# Connectors.net
KiCad netlist of a schematic drawn in Altium Designer
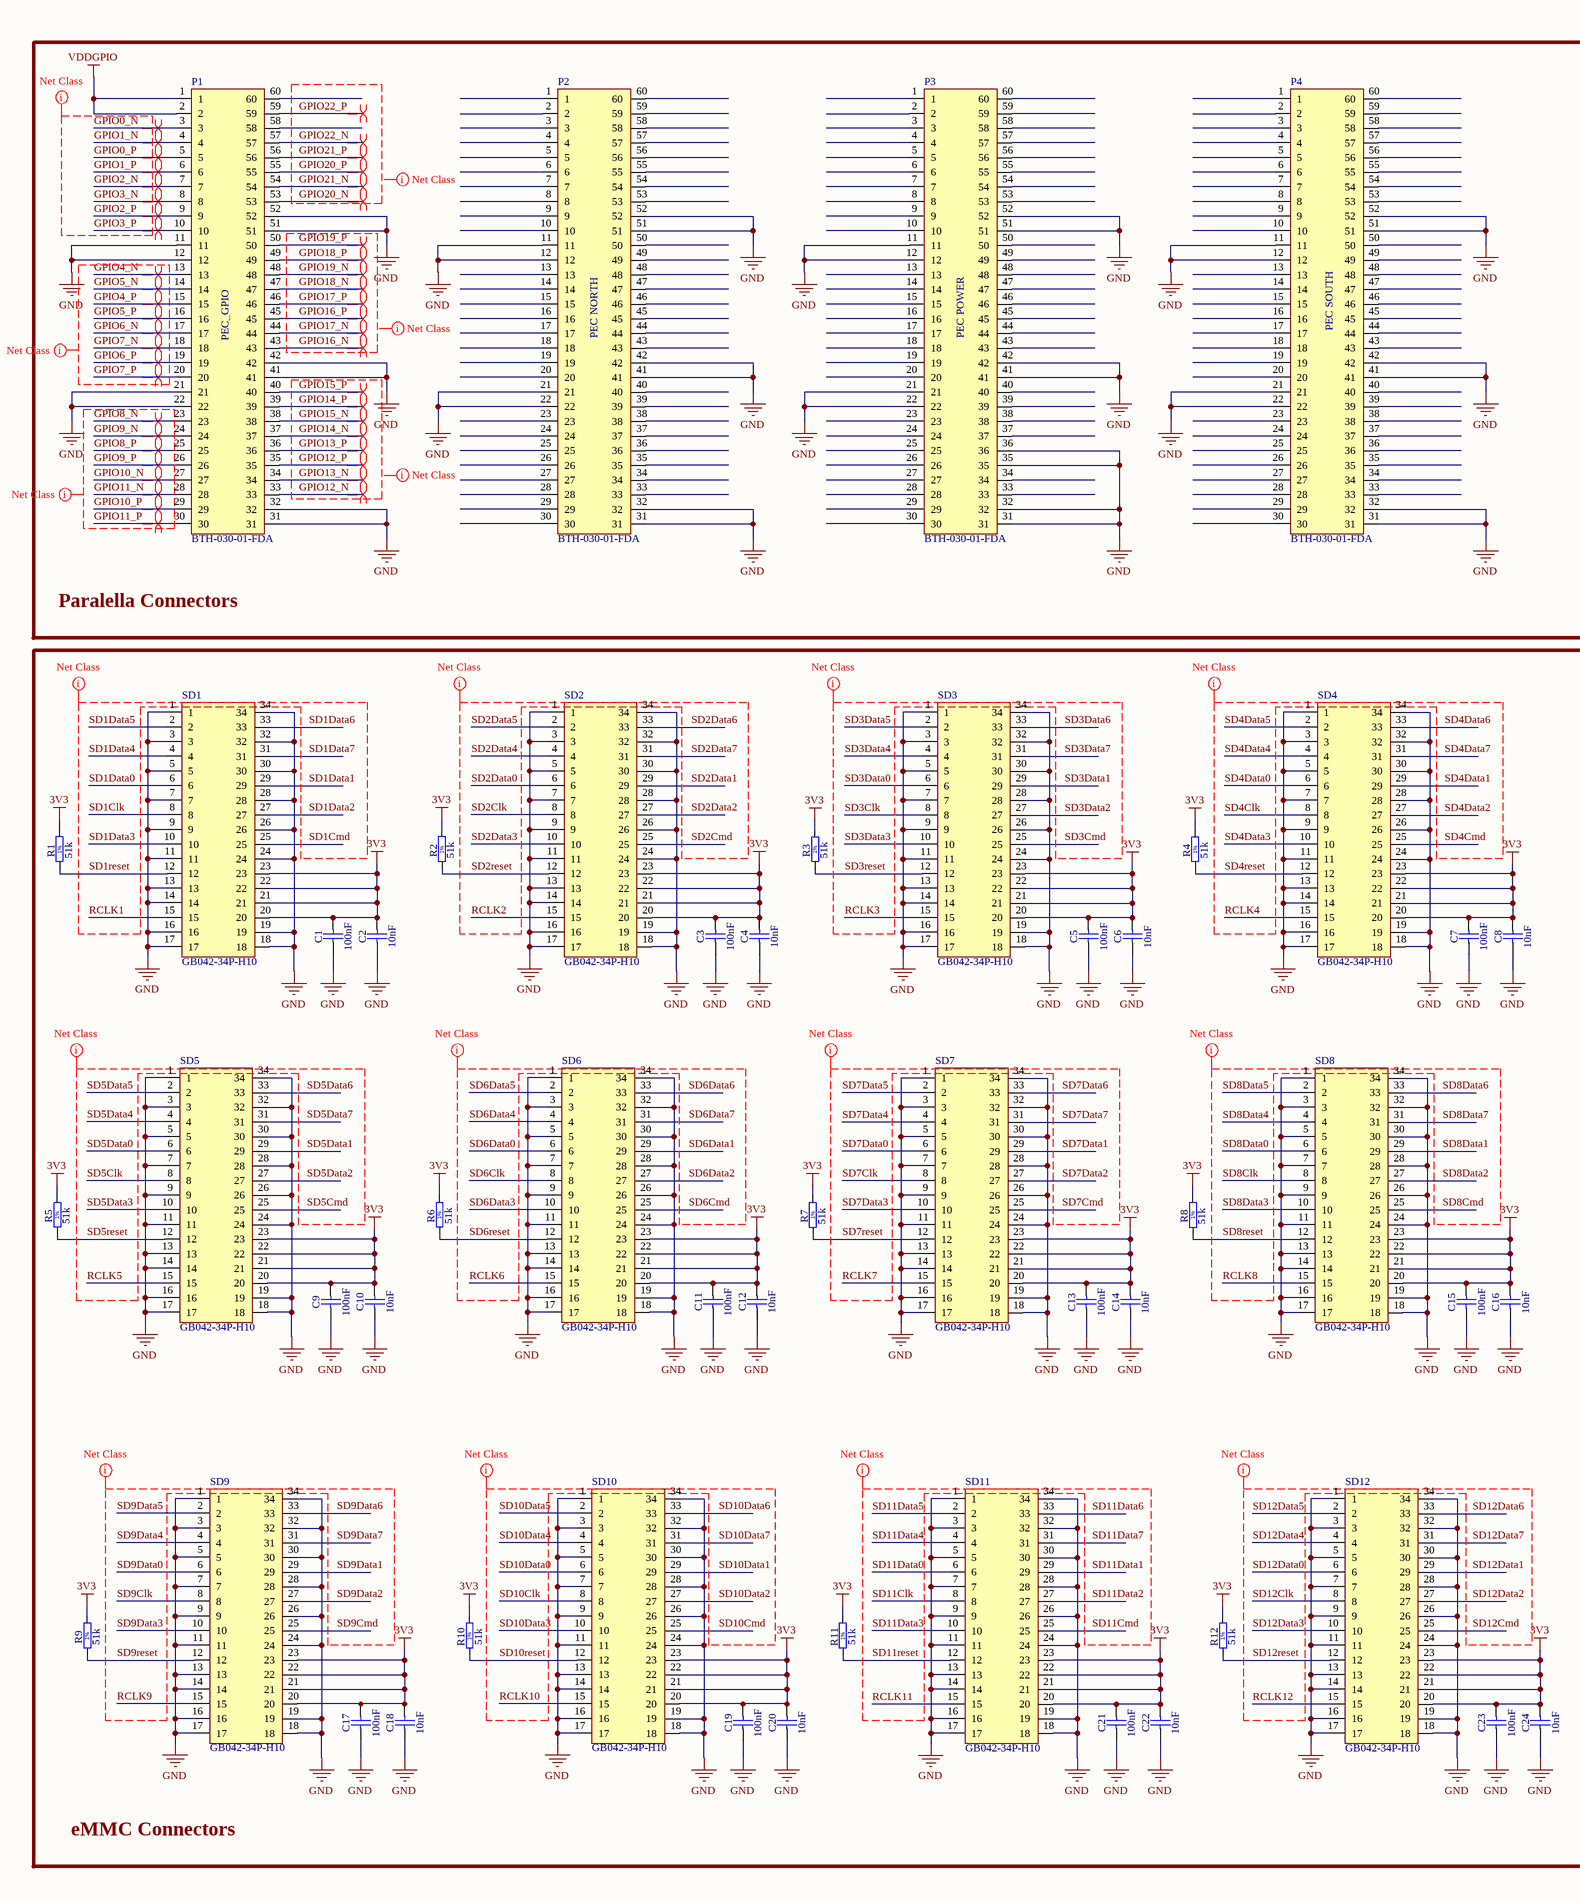
[diagram p0: Connectors.SchDoc, left]
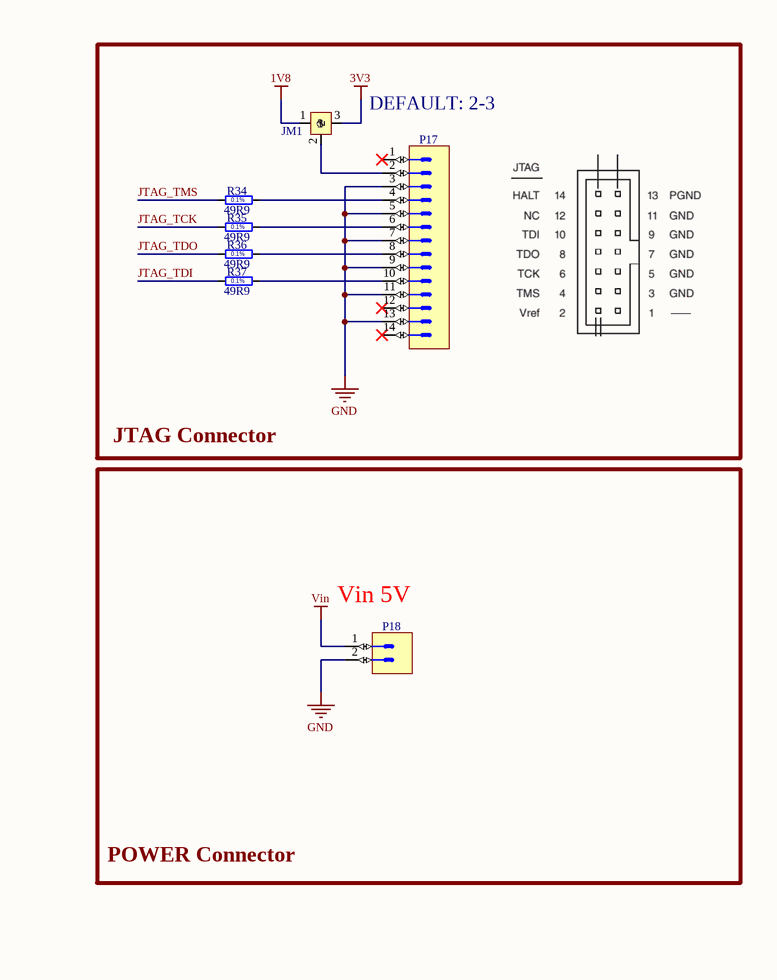
[diagram p1: Connectors.SchDoc, right]

(export (version "E")
  (design (tool "Eeschema 10.0.6"))
  (components
    (comp (ref "C1")
      (value "100nF")
      (footprint "CAPC1608X87N")
      (description "Non-polarised capacitor")
      (fields
        (field (name "PART NUMBER") "CC0603_100NF_50V_10%_X7R")
        (field (name "VOLTAGE") "50V")
        (field (name "AUTHOR") "CERN DEM JLC")
      )
      (libsource (lib "Capacitors") (part "Capacitor - non polarized"))
    )
    (comp (ref "C2")
      (value "10nF")
      (footprint "CAPC1608X87N")
      (description "Non-polarised capacitor")
      (fields
        (field (name "PART NUMBER") "CC0603_10NF_50V_10%_X7R")
        (field (name "VOLTAGE") "50V")
        (field (name "AUTHOR") "CERN DEM JLC")
      )
      (libsource (lib "Capacitors") (part "Capacitor - non polarized"))
    )
    (comp (ref "C3")
      (value "100nF")
      (footprint "CAPC1608X87N")
      (description "Non-polarised capacitor")
      (fields
        (field (name "PART NUMBER") "CC0603_100NF_50V_10%_X7R")
        (field (name "VOLTAGE") "50V")
        (field (name "AUTHOR") "CERN DEM JLC")
      )
      (libsource (lib "Capacitors") (part "Capacitor - non polarized"))
    )
    (comp (ref "C4")
      (value "10nF")
      (footprint "CAPC1608X87N")
      (description "Non-polarised capacitor")
      (fields
        (field (name "PART NUMBER") "CC0603_10NF_50V_10%_X7R")
        (field (name "VOLTAGE") "50V")
        (field (name "AUTHOR") "CERN DEM JLC")
      )
      (libsource (lib "Capacitors") (part "Capacitor - non polarized"))
    )
    (comp (ref "C5")
      (value "100nF")
      (footprint "CAPC1608X87N")
      (description "Non-polarised capacitor")
      (fields
        (field (name "PART NUMBER") "CC0603_100NF_50V_10%_X7R")
        (field (name "VOLTAGE") "50V")
        (field (name "AUTHOR") "CERN DEM JLC")
      )
      (libsource (lib "Capacitors") (part "Capacitor - non polarized"))
    )
    (comp (ref "C6")
      (value "10nF")
      (footprint "CAPC1608X87N")
      (description "Non-polarised capacitor")
      (fields
        (field (name "PART NUMBER") "CC0603_10NF_50V_10%_X7R")
        (field (name "VOLTAGE") "50V")
        (field (name "AUTHOR") "CERN DEM JLC")
      )
      (libsource (lib "Capacitors") (part "Capacitor - non polarized"))
    )
    (comp (ref "C7")
      (value "100nF")
      (footprint "CAPC1608X87N")
      (description "Non-polarised capacitor")
      (fields
        (field (name "PART NUMBER") "CC0603_100NF_50V_10%_X7R")
        (field (name "VOLTAGE") "50V")
        (field (name "AUTHOR") "CERN DEM JLC")
      )
      (libsource (lib "Capacitors") (part "Capacitor - non polarized"))
    )
    (comp (ref "C8")
      (value "10nF")
      (footprint "CAPC1608X87N")
      (description "Non-polarised capacitor")
      (fields
        (field (name "PART NUMBER") "CC0603_10NF_50V_10%_X7R")
        (field (name "VOLTAGE") "50V")
        (field (name "AUTHOR") "CERN DEM JLC")
      )
      (libsource (lib "Capacitors") (part "Capacitor - non polarized"))
    )
    (comp (ref "C9")
      (value "100nF")
      (footprint "CAPC1608X87N")
      (description "Non-polarised capacitor")
      (fields
        (field (name "PART NUMBER") "CC0603_100NF_50V_10%_X7R")
        (field (name "VOLTAGE") "50V")
        (field (name "AUTHOR") "CERN DEM JLC")
      )
      (libsource (lib "Capacitors") (part "Capacitor - non polarized"))
    )
    (comp (ref "C10")
      (value "10nF")
      (footprint "CAPC1608X87N")
      (description "Non-polarised capacitor")
      (fields
        (field (name "PART NUMBER") "CC0603_10NF_50V_10%_X7R")
        (field (name "VOLTAGE") "50V")
        (field (name "AUTHOR") "CERN DEM JLC")
      )
      (libsource (lib "Capacitors") (part "Capacitor - non polarized"))
    )
    (comp (ref "C11")
      (value "100nF")
      (footprint "CAPC1608X87N")
      (description "Non-polarised capacitor")
      (fields
        (field (name "PART NUMBER") "CC0603_100NF_50V_10%_X7R")
        (field (name "VOLTAGE") "50V")
        (field (name "AUTHOR") "CERN DEM JLC")
      )
      (libsource (lib "Capacitors") (part "Capacitor - non polarized"))
    )
    (comp (ref "C12")
      (value "10nF")
      (footprint "CAPC1608X87N")
      (description "Non-polarised capacitor")
      (fields
        (field (name "PART NUMBER") "CC0603_10NF_50V_10%_X7R")
        (field (name "VOLTAGE") "50V")
        (field (name "AUTHOR") "CERN DEM JLC")
      )
      (libsource (lib "Capacitors") (part "Capacitor - non polarized"))
    )
    (comp (ref "C13")
      (value "100nF")
      (footprint "CAPC1608X87N")
      (description "Non-polarised capacitor")
      (fields
        (field (name "PART NUMBER") "CC0603_100NF_50V_10%_X7R")
        (field (name "VOLTAGE") "50V")
        (field (name "AUTHOR") "CERN DEM JLC")
      )
      (libsource (lib "Capacitors") (part "Capacitor - non polarized"))
    )
    (comp (ref "C14")
      (value "10nF")
      (footprint "CAPC1608X87N")
      (description "Non-polarised capacitor")
      (fields
        (field (name "PART NUMBER") "CC0603_10NF_50V_10%_X7R")
        (field (name "VOLTAGE") "50V")
        (field (name "AUTHOR") "CERN DEM JLC")
      )
      (libsource (lib "Capacitors") (part "Capacitor - non polarized"))
    )
    (comp (ref "C15")
      (value "100nF")
      (footprint "CAPC1608X87N")
      (description "Non-polarised capacitor")
      (fields
        (field (name "PART NUMBER") "CC0603_100NF_50V_10%_X7R")
        (field (name "VOLTAGE") "50V")
        (field (name "AUTHOR") "CERN DEM JLC")
      )
      (libsource (lib "Capacitors") (part "Capacitor - non polarized"))
    )
    (comp (ref "C16")
      (value "10nF")
      (footprint "CAPC1608X87N")
      (description "Non-polarised capacitor")
      (fields
        (field (name "PART NUMBER") "CC0603_10NF_50V_10%_X7R")
        (field (name "VOLTAGE") "50V")
        (field (name "AUTHOR") "CERN DEM JLC")
      )
      (libsource (lib "Capacitors") (part "Capacitor - non polarized"))
    )
    (comp (ref "C17")
      (value "100nF")
      (footprint "CAPC1608X87N")
      (description "Non-polarised capacitor")
      (fields
        (field (name "PART NUMBER") "CC0603_100NF_50V_10%_X7R")
        (field (name "VOLTAGE") "50V")
        (field (name "AUTHOR") "CERN DEM JLC")
      )
      (libsource (lib "Capacitors") (part "Capacitor - non polarized"))
    )
    (comp (ref "C18")
      (value "10nF")
      (footprint "CAPC1608X87N")
      (description "Non-polarised capacitor")
      (fields
        (field (name "PART NUMBER") "CC0603_10NF_50V_10%_X7R")
        (field (name "VOLTAGE") "50V")
        (field (name "AUTHOR") "CERN DEM JLC")
      )
      (libsource (lib "Capacitors") (part "Capacitor - non polarized"))
    )
    (comp (ref "C19")
      (value "100nF")
      (footprint "CAPC1608X87N")
      (description "Non-polarised capacitor")
      (fields
        (field (name "PART NUMBER") "CC0603_100NF_50V_10%_X7R")
        (field (name "VOLTAGE") "50V")
        (field (name "AUTHOR") "CERN DEM JLC")
      )
      (libsource (lib "Capacitors") (part "Capacitor - non polarized"))
    )
    (comp (ref "C20")
      (value "10nF")
      (footprint "CAPC1608X87N")
      (description "Non-polarised capacitor")
      (fields
        (field (name "PART NUMBER") "CC0603_10NF_50V_10%_X7R")
        (field (name "VOLTAGE") "50V")
        (field (name "AUTHOR") "CERN DEM JLC")
      )
      (libsource (lib "Capacitors") (part "Capacitor - non polarized"))
    )
    (comp (ref "C21")
      (value "100nF")
      (footprint "CAPC1608X87N")
      (description "Non-polarised capacitor")
      (fields
        (field (name "PART NUMBER") "CC0603_100NF_50V_10%_X7R")
        (field (name "VOLTAGE") "50V")
        (field (name "AUTHOR") "CERN DEM JLC")
      )
      (libsource (lib "Capacitors") (part "Capacitor - non polarized"))
    )
    (comp (ref "C22")
      (value "10nF")
      (footprint "CAPC1608X87N")
      (description "Non-polarised capacitor")
      (fields
        (field (name "PART NUMBER") "CC0603_10NF_50V_10%_X7R")
        (field (name "VOLTAGE") "50V")
        (field (name "AUTHOR") "CERN DEM JLC")
      )
      (libsource (lib "Capacitors") (part "Capacitor - non polarized"))
    )
    (comp (ref "C23")
      (value "100nF")
      (footprint "CAPC1608X87N")
      (description "Non-polarised capacitor")
      (fields
        (field (name "PART NUMBER") "CC0603_100NF_50V_10%_X7R")
        (field (name "VOLTAGE") "50V")
        (field (name "AUTHOR") "CERN DEM JLC")
      )
      (libsource (lib "Capacitors") (part "Capacitor - non polarized"))
    )
    (comp (ref "C24")
      (value "10nF")
      (footprint "CAPC1608X87N")
      (description "Non-polarised capacitor")
      (fields
        (field (name "PART NUMBER") "CC0603_10NF_50V_10%_X7R")
        (field (name "VOLTAGE") "50V")
        (field (name "AUTHOR") "CERN DEM JLC")
      )
      (libsource (lib "Capacitors") (part "Capacitor - non polarized"))
    )
    (comp (ref "JM1")
      (value "Jumper 0R")
      (footprint "JUMPER_0R")
      (libsource (lib "SCHLIB") (part "Jumper 0R"))
    )
    (comp (ref "P1")
      (value "BTH-030-01-FDA")
      (footprint "BTH-030-01-F-D-A")
      (description "Connector Parallela")
      (libsource (lib "SCHLIB") (part "BTH-030-01-FDA"))
    )
    (comp (ref "P2")
      (value "BTH-030-01-FDA")
      (footprint "BTH-030-01-F-D-A")
      (description "Connector Parallela")
      (libsource (lib "SCHLIB") (part "BTH-030-01-FDA"))
    )
    (comp (ref "P3")
      (value "BTH-030-01-FDA")
      (footprint "BTH-030-01-F-D-A")
      (description "Connector Parallela")
      (libsource (lib "SCHLIB") (part "BTH-030-01-FDA"))
    )
    (comp (ref "P4")
      (value "BTH-030-01-FDA")
      (footprint "BTH-030-01-F-D-A")
      (description "Connector Parallela")
      (libsource (lib "SCHLIB") (part "BTH-030-01-FDA"))
    )
    (comp (ref "P17")
      (value "~")
      (description "Connector 14 Male")
      (fields
        (field (name "MANUFACTURER PART NUMBER") "0878321420")
        (field (name "MANUFACTURER") "Molex, LLC")
      )
      (libsource (lib "Connectors") (part "Connector 14 Male"))
    )
    (comp (ref "P18")
      (value "KK®")
      (footprint "MOLEX_26-60-4020")
      (description "Connector 2 Male")
      (fields
        (field (name "PART NUMBER") "MOLEX_26-60-4020")
        (field (name "MANUFACTURER") "Molex, LLC")
        (field (name "AUTHOR") "CERN DEM JLC")
      )
      (libsource (lib "Connectors") (part "Connector 2 Male"))
    )
    (comp (ref "R1")
      (value "51k")
      (footprint "RESC1608X55N")
      (description "Resistor - 1%")
      (fields
        (field (name "PART NUMBER") "R0603_51K_1%_0.1W_100PPM")
        (field (name "POWER") "0.1W")
        (field (name "AUTHOR") "CERN DEM JLC")
      )
      (libsource (lib "Resistors") (part "Resistor - 1%"))
    )
    (comp (ref "R2")
      (value "51k")
      (footprint "RESC1608X55N")
      (description "Resistor - 1%")
      (fields
        (field (name "PART NUMBER") "R0603_51K_1%_0.1W_100PPM")
        (field (name "POWER") "0.1W")
        (field (name "AUTHOR") "CERN DEM JLC")
      )
      (libsource (lib "Resistors") (part "Resistor - 1%"))
    )
    (comp (ref "R3")
      (value "51k")
      (footprint "RESC1608X55N")
      (description "Resistor - 1%")
      (fields
        (field (name "PART NUMBER") "R0603_51K_1%_0.1W_100PPM")
        (field (name "POWER") "0.1W")
        (field (name "AUTHOR") "CERN DEM JLC")
      )
      (libsource (lib "Resistors") (part "Resistor - 1%"))
    )
    (comp (ref "R4")
      (value "51k")
      (footprint "RESC1608X55N")
      (description "Resistor - 1%")
      (fields
        (field (name "PART NUMBER") "R0603_51K_1%_0.1W_100PPM")
        (field (name "POWER") "0.1W")
        (field (name "AUTHOR") "CERN DEM JLC")
      )
      (libsource (lib "Resistors") (part "Resistor - 1%"))
    )
    (comp (ref "R5")
      (value "51k")
      (footprint "RESC1608X55N")
      (description "Resistor - 1%")
      (fields
        (field (name "PART NUMBER") "R0603_51K_1%_0.1W_100PPM")
        (field (name "POWER") "0.1W")
        (field (name "AUTHOR") "CERN DEM JLC")
      )
      (libsource (lib "Resistors") (part "Resistor - 1%"))
    )
    (comp (ref "R6")
      (value "51k")
      (footprint "RESC1608X55N")
      (description "Resistor - 1%")
      (fields
        (field (name "PART NUMBER") "R0603_51K_1%_0.1W_100PPM")
        (field (name "POWER") "0.1W")
        (field (name "AUTHOR") "CERN DEM JLC")
      )
      (libsource (lib "Resistors") (part "Resistor - 1%"))
    )
    (comp (ref "R7")
      (value "51k")
      (footprint "RESC1608X55N")
      (description "Resistor - 1%")
      (fields
        (field (name "PART NUMBER") "R0603_51K_1%_0.1W_100PPM")
        (field (name "POWER") "0.1W")
        (field (name "AUTHOR") "CERN DEM JLC")
      )
      (libsource (lib "Resistors") (part "Resistor - 1%"))
    )
    (comp (ref "R8")
      (value "51k")
      (footprint "RESC1608X55N")
      (description "Resistor - 1%")
      (fields
        (field (name "PART NUMBER") "R0603_51K_1%_0.1W_100PPM")
        (field (name "POWER") "0.1W")
        (field (name "AUTHOR") "CERN DEM JLC")
      )
      (libsource (lib "Resistors") (part "Resistor - 1%"))
    )
    (comp (ref "R9")
      (value "51k")
      (footprint "RESC1608X55N")
      (description "Resistor - 1%")
      (fields
        (field (name "PART NUMBER") "R0603_51K_1%_0.1W_100PPM")
        (field (name "POWER") "0.1W")
        (field (name "AUTHOR") "CERN DEM JLC")
      )
      (libsource (lib "Resistors") (part "Resistor - 1%"))
    )
    (comp (ref "R10")
      (value "51k")
      (footprint "RESC1608X55N")
      (description "Resistor - 1%")
      (fields
        (field (name "PART NUMBER") "R0603_51K_1%_0.1W_100PPM")
        (field (name "POWER") "0.1W")
        (field (name "AUTHOR") "CERN DEM JLC")
      )
      (libsource (lib "Resistors") (part "Resistor - 1%"))
    )
    (comp (ref "R11")
      (value "51k")
      (footprint "RESC1608X55N")
      (description "Resistor - 1%")
      (fields
        (field (name "PART NUMBER") "R0603_51K_1%_0.1W_100PPM")
        (field (name "POWER") "0.1W")
        (field (name "AUTHOR") "CERN DEM JLC")
      )
      (libsource (lib "Resistors") (part "Resistor - 1%"))
    )
    (comp (ref "R12")
      (value "51k")
      (footprint "RESC1608X55N")
      (description "Resistor - 1%")
      (fields
        (field (name "PART NUMBER") "R0603_51K_1%_0.1W_100PPM")
        (field (name "POWER") "0.1W")
        (field (name "AUTHOR") "CERN DEM JLC")
      )
      (libsource (lib "Resistors") (part "Resistor - 1%"))
    )
    (comp (ref "R34")
      (value "49R9")
      (footprint "RESC1608X55N")
      (description "Resistor - 0.1%")
      (fields
        (field (name "PART NUMBER") "R0603_49R9_0.1%_0.063W_10PPM")
        (field (name "POWER") "0.063W")
        (field (name "AUTHOR") "CERN DEM JLC")
      )
      (libsource (lib "Resistors") (part "Resistor - 0.1%"))
    )
    (comp (ref "R35")
      (value "49R9")
      (footprint "RESC1608X55N")
      (description "Resistor - 0.1%")
      (fields
        (field (name "PART NUMBER") "R0603_49R9_0.1%_0.063W_10PPM")
        (field (name "POWER") "0.063W")
        (field (name "AUTHOR") "CERN DEM JLC")
      )
      (libsource (lib "Resistors") (part "Resistor - 0.1%"))
    )
    (comp (ref "R36")
      (value "49R9")
      (footprint "RESC1608X55N")
      (description "Resistor - 0.1%")
      (fields
        (field (name "PART NUMBER") "R0603_49R9_0.1%_0.063W_10PPM")
        (field (name "POWER") "0.063W")
        (field (name "AUTHOR") "CERN DEM JLC")
      )
      (libsource (lib "Resistors") (part "Resistor - 0.1%"))
    )
    (comp (ref "R37")
      (value "49R9")
      (footprint "RESC1608X55N")
      (description "Resistor - 0.1%")
      (fields
        (field (name "PART NUMBER") "R0603_49R9_0.1%_0.063W_10PPM")
        (field (name "POWER") "0.063W")
        (field (name "AUTHOR") "CERN DEM JLC")
      )
      (libsource (lib "Resistors") (part "Resistor - 0.1%"))
    )
    (comp (ref "SD1")
      (value "GB042-34P-H10")
      (footprint "GB042-34P-H10")
      (description "Connector, eMMC")
      (libsource (lib "SCHLIB") (part "GB042-34P-H10"))
    )
    (comp (ref "SD2")
      (value "GB042-34P-H10")
      (footprint "GB042-34P-H10")
      (description "Connector, eMMC")
      (libsource (lib "SCHLIB") (part "GB042-34P-H10"))
    )
    (comp (ref "SD3")
      (value "GB042-34P-H10")
      (footprint "GB042-34P-H10")
      (description "Connector, eMMC")
      (libsource (lib "SCHLIB") (part "GB042-34P-H10"))
    )
    (comp (ref "SD4")
      (value "GB042-34P-H10")
      (footprint "GB042-34P-H10")
      (description "Connector, eMMC")
      (libsource (lib "SCHLIB") (part "GB042-34P-H10"))
    )
    (comp (ref "SD5")
      (value "GB042-34P-H10")
      (footprint "GB042-34P-H10")
      (description "Connector, eMMC")
      (libsource (lib "SCHLIB") (part "GB042-34P-H10"))
    )
    (comp (ref "SD6")
      (value "GB042-34P-H10")
      (footprint "GB042-34P-H10")
      (description "Connector, eMMC")
      (libsource (lib "SCHLIB") (part "GB042-34P-H10"))
    )
    (comp (ref "SD7")
      (value "GB042-34P-H10")
      (footprint "GB042-34P-H10")
      (description "Connector, eMMC")
      (libsource (lib "SCHLIB") (part "GB042-34P-H10"))
    )
    (comp (ref "SD8")
      (value "GB042-34P-H10")
      (footprint "GB042-34P-H10")
      (description "Connector, eMMC")
      (libsource (lib "SCHLIB") (part "GB042-34P-H10"))
    )
    (comp (ref "SD9")
      (value "GB042-34P-H10")
      (footprint "GB042-34P-H10")
      (description "Connector, eMMC")
      (libsource (lib "SCHLIB") (part "GB042-34P-H10"))
    )
    (comp (ref "SD10")
      (value "GB042-34P-H10")
      (footprint "GB042-34P-H10")
      (description "Connector, eMMC")
      (libsource (lib "SCHLIB") (part "GB042-34P-H10"))
    )
    (comp (ref "SD11")
      (value "GB042-34P-H10")
      (footprint "GB042-34P-H10")
      (description "Connector, eMMC")
      (libsource (lib "SCHLIB") (part "GB042-34P-H10"))
    )
    (comp (ref "SD12")
      (value "GB042-34P-H10")
      (footprint "GB042-34P-H10")
      (description "Connector, eMMC")
      (libsource (lib "SCHLIB") (part "GB042-34P-H10"))
    )
  )
  (nets
    (net (code "1") (name "/GPIO0_N") (class "Default")
      (node (ref "P1") (pin "3") (pinfunction "3_3") (pintype "passive"))
    )
    (net (code "2") (name "/GPIO0_P") (class "Default")
      (node (ref "P1") (pin "5") (pinfunction "5_5") (pintype "passive"))
    )
    (net (code "3") (name "/GPIO1_N") (class "Default")
      (node (ref "P1") (pin "4") (pinfunction "4_4") (pintype "passive"))
    )
    (net (code "4") (name "/GPIO1_P") (class "Default")
      (node (ref "P1") (pin "6") (pinfunction "6_6") (pintype "passive"))
    )
    (net (code "5") (name "/GPIO2_N") (class "Default")
      (node (ref "P1") (pin "7") (pinfunction "7_7") (pintype "passive"))
    )
    (net (code "6") (name "/GPIO2_P") (class "Default")
      (node (ref "P1") (pin "9") (pinfunction "9_9") (pintype "passive"))
    )
    (net (code "7") (name "/GPIO3_N") (class "Default")
      (node (ref "P1") (pin "8") (pinfunction "8_8") (pintype "passive"))
    )
    (net (code "8") (name "/GPIO3_P") (class "Default")
      (node (ref "P1") (pin "10") (pinfunction "10_10") (pintype "passive"))
    )
    (net (code "9") (name "/GPIO4_N") (class "Default")
      (node (ref "P1") (pin "13") (pinfunction "13_13") (pintype "passive"))
    )
    (net (code "10") (name "/GPIO4_P") (class "Default")
      (node (ref "P1") (pin "15") (pinfunction "15_15") (pintype "passive"))
    )
    (net (code "11") (name "/GPIO5_N") (class "Default")
      (node (ref "P1") (pin "14") (pinfunction "14_14") (pintype "passive"))
    )
    (net (code "12") (name "/GPIO5_P") (class "Default")
      (node (ref "P1") (pin "16") (pinfunction "16_16") (pintype "passive"))
    )
    (net (code "13") (name "/GPIO6_N") (class "Default")
      (node (ref "P1") (pin "17") (pinfunction "17_17") (pintype "passive"))
    )
    (net (code "14") (name "/GPIO6_P") (class "Default")
      (node (ref "P1") (pin "19") (pinfunction "19_19") (pintype "passive"))
    )
    (net (code "15") (name "/GPIO7_N") (class "Default")
      (node (ref "P1") (pin "18") (pinfunction "18_18") (pintype "passive"))
    )
    (net (code "16") (name "/GPIO7_P") (class "Default")
      (node (ref "P1") (pin "20") (pinfunction "20_20") (pintype "passive"))
    )
    (net (code "17") (name "/GPIO8_N") (class "Default")
      (node (ref "P1") (pin "23") (pinfunction "23_23") (pintype "passive"))
    )
    (net (code "18") (name "/GPIO8_P") (class "Default")
      (node (ref "P1") (pin "25") (pinfunction "25_25") (pintype "passive"))
    )
    (net (code "19") (name "/GPIO9_N") (class "Default")
      (node (ref "P1") (pin "24") (pinfunction "24_24") (pintype "passive"))
    )
    (net (code "20") (name "/GPIO9_P") (class "Default")
      (node (ref "P1") (pin "26") (pinfunction "26_26") (pintype "passive"))
    )
    (net (code "21") (name "/GPIO10_N") (class "Default")
      (node (ref "P1") (pin "27") (pinfunction "27_27") (pintype "passive"))
    )
    (net (code "22") (name "/GPIO10_P") (class "Default")
      (node (ref "P1") (pin "29") (pinfunction "29_29") (pintype "passive"))
    )
    (net (code "23") (name "/GPIO11_N") (class "Default")
      (node (ref "P1") (pin "28") (pinfunction "28_28") (pintype "passive"))
    )
    (net (code "24") (name "/GPIO11_P") (class "Default")
      (node (ref "P1") (pin "30") (pinfunction "30_30") (pintype "passive"))
    )
    (net (code "25") (name "/GPIO12_N") (class "Default")
      (node (ref "P1") (pin "33") (pinfunction "33_33") (pintype "passive"))
    )
    (net (code "26") (name "/GPIO12_P") (class "Default")
      (node (ref "P1") (pin "35") (pinfunction "35_35") (pintype "passive"))
    )
    (net (code "27") (name "/GPIO13_N") (class "Default")
      (node (ref "P1") (pin "34") (pinfunction "34_34") (pintype "passive"))
    )
    (net (code "28") (name "/GPIO13_P") (class "Default")
      (node (ref "P1") (pin "36") (pinfunction "36_36") (pintype "passive"))
    )
    (net (code "29") (name "/GPIO14_N") (class "Default")
      (node (ref "P1") (pin "37") (pinfunction "37_37") (pintype "passive"))
    )
    (net (code "30") (name "/GPIO14_P") (class "Default")
      (node (ref "P1") (pin "39") (pinfunction "39_39") (pintype "passive"))
    )
    (net (code "31") (name "/GPIO15_N") (class "Default")
      (node (ref "P1") (pin "38") (pinfunction "38_38") (pintype "passive"))
    )
    (net (code "32") (name "/GPIO15_P") (class "Default")
      (node (ref "P1") (pin "40") (pinfunction "40_40") (pintype "passive"))
    )
    (net (code "33") (name "/GPIO16_N") (class "Default")
      (node (ref "P1") (pin "43") (pinfunction "43_43") (pintype "passive"))
    )
    (net (code "34") (name "/GPIO16_P") (class "Default")
      (node (ref "P1") (pin "45") (pinfunction "45_45") (pintype "passive"))
    )
    (net (code "35") (name "/GPIO17_N") (class "Default")
      (node (ref "P1") (pin "44") (pinfunction "44_44") (pintype "passive"))
    )
    (net (code "36") (name "/GPIO17_P") (class "Default")
      (node (ref "P1") (pin "46") (pinfunction "46_46") (pintype "passive"))
    )
    (net (code "37") (name "/GPIO18_N") (class "Default")
      (node (ref "P1") (pin "47") (pinfunction "47_47") (pintype "passive"))
    )
    (net (code "38") (name "/GPIO18_P") (class "Default")
      (node (ref "P1") (pin "49") (pinfunction "49_49") (pintype "passive"))
    )
    (net (code "39") (name "/GPIO19_N") (class "Default")
      (node (ref "P1") (pin "48") (pinfunction "48_48") (pintype "passive"))
    )
    (net (code "40") (name "/GPIO19_P") (class "Default")
      (node (ref "P1") (pin "50") (pinfunction "50_50") (pintype "passive"))
    )
    (net (code "41") (name "/GPIO20_N") (class "Default")
      (node (ref "P1") (pin "53") (pinfunction "53_53") (pintype "passive"))
    )
    (net (code "42") (name "/GPIO20_P") (class "Default")
      (node (ref "P1") (pin "55") (pinfunction "55_55") (pintype "passive"))
    )
    (net (code "43") (name "/GPIO21_N") (class "Default")
      (node (ref "P1") (pin "54") (pinfunction "54_54") (pintype "passive"))
    )
    (net (code "44") (name "/GPIO21_P") (class "Default")
      (node (ref "P1") (pin "56") (pinfunction "56_56") (pintype "passive"))
    )
    (net (code "45") (name "/GPIO22_N") (class "Default")
      (node (ref "P1") (pin "57") (pinfunction "57_57") (pintype "passive"))
    )
    (net (code "46") (name "/GPIO22_P") (class "Default")
      (node (ref "P1") (pin "59") (pinfunction "59_59") (pintype "passive"))
    )
    (net (code "47") (name "/JTAG_TCK") (class "Default")
      (node (ref "R35") (pin "1") (pinfunction "1_1") (pintype "passive"))
    )
    (net (code "48") (name "/JTAG_TDI") (class "Default")
      (node (ref "R37") (pin "1") (pinfunction "1_1") (pintype "passive"))
    )
    (net (code "49") (name "/JTAG_TDO") (class "Default")
      (node (ref "R36") (pin "1") (pinfunction "1_1") (pintype "passive"))
    )
    (net (code "50") (name "/JTAG_TMS") (class "Default")
      (node (ref "R34") (pin "1") (pinfunction "1_1") (pintype "passive"))
    )
    (net (code "51") (name "/RCLK1") (class "Default")
      (node (ref "SD1") (pin "15") (pinfunction "15_15") (pintype "passive"))
    )
    (net (code "52") (name "/RCLK2") (class "Default")
      (node (ref "SD2") (pin "15") (pinfunction "15_15") (pintype "passive"))
    )
    (net (code "53") (name "/RCLK3") (class "Default")
      (node (ref "SD3") (pin "15") (pinfunction "15_15") (pintype "passive"))
    )
    (net (code "54") (name "/RCLK4") (class "Default")
      (node (ref "SD4") (pin "15") (pinfunction "15_15") (pintype "passive"))
    )
    (net (code "55") (name "/RCLK5") (class "Default")
      (node (ref "SD5") (pin "15") (pinfunction "15_15") (pintype "passive"))
    )
    (net (code "56") (name "/RCLK6") (class "Default")
      (node (ref "SD6") (pin "15") (pinfunction "15_15") (pintype "passive"))
    )
    (net (code "57") (name "/RCLK7") (class "Default")
      (node (ref "SD7") (pin "15") (pinfunction "15_15") (pintype "passive"))
    )
    (net (code "58") (name "/RCLK8") (class "Default")
      (node (ref "SD8") (pin "15") (pinfunction "15_15") (pintype "passive"))
    )
    (net (code "59") (name "/RCLK9") (class "Default")
      (node (ref "SD9") (pin "15") (pinfunction "15_15") (pintype "passive"))
    )
    (net (code "60") (name "/RCLK10") (class "Default")
      (node (ref "SD10") (pin "15") (pinfunction "15_15") (pintype "passive"))
    )
    (net (code "61") (name "/RCLK11") (class "Default")
      (node (ref "SD11") (pin "15") (pinfunction "15_15") (pintype "passive"))
    )
    (net (code "62") (name "/RCLK12") (class "Default")
      (node (ref "SD12") (pin "15") (pinfunction "15_15") (pintype "passive"))
    )
    (net (code "63") (name "/SD1Clk") (class "Default")
      (node (ref "SD1") (pin "8") (pinfunction "8_8") (pintype "passive"))
    )
    (net (code "64") (name "/SD1Cmd") (class "Default")
      (node (ref "SD1") (pin "25") (pinfunction "25_25") (pintype "passive"))
    )
    (net (code "65") (name "/SD1Data0") (class "Default")
      (node (ref "SD1") (pin "6") (pinfunction "6_6") (pintype "passive"))
    )
    (net (code "66") (name "/SD1Data1") (class "Default")
      (node (ref "SD1") (pin "29") (pinfunction "29_29") (pintype "passive"))
    )
    (net (code "67") (name "/SD1Data2") (class "Default")
      (node (ref "SD1") (pin "27") (pinfunction "27_27") (pintype "passive"))
    )
    (net (code "68") (name "/SD1Data3") (class "Default")
      (node (ref "SD1") (pin "10") (pinfunction "10_10") (pintype "passive"))
    )
    (net (code "69") (name "/SD1Data4") (class "Default")
      (node (ref "SD1") (pin "4") (pinfunction "4_4") (pintype "passive"))
    )
    (net (code "70") (name "/SD1Data5") (class "Default")
      (node (ref "SD1") (pin "2") (pinfunction "2_2") (pintype "passive"))
    )
    (net (code "71") (name "/SD1Data6") (class "Default")
      (node (ref "SD1") (pin "33") (pinfunction "33_33") (pintype "passive"))
    )
    (net (code "72") (name "/SD1Data7") (class "Default")
      (node (ref "SD1") (pin "31") (pinfunction "31_31") (pintype "passive"))
    )
    (net (code "73") (name "/SD1reset") (class "Default")
      (node (ref "R1") (pin "1") (pinfunction "1_1") (pintype "passive"))
      (node (ref "SD1") (pin "12") (pinfunction "12_12") (pintype "passive"))
    )
    (net (code "74") (name "/SD2Clk") (class "Default")
      (node (ref "SD2") (pin "8") (pinfunction "8_8") (pintype "passive"))
    )
    (net (code "75") (name "/SD2Cmd") (class "Default")
      (node (ref "SD2") (pin "25") (pinfunction "25_25") (pintype "passive"))
    )
    (net (code "76") (name "/SD2Data0") (class "Default")
      (node (ref "SD2") (pin "6") (pinfunction "6_6") (pintype "passive"))
    )
    (net (code "77") (name "/SD2Data1") (class "Default")
      (node (ref "SD2") (pin "29") (pinfunction "29_29") (pintype "passive"))
    )
    (net (code "78") (name "/SD2Data2") (class "Default")
      (node (ref "SD2") (pin "27") (pinfunction "27_27") (pintype "passive"))
    )
    (net (code "79") (name "/SD2Data3") (class "Default")
      (node (ref "SD2") (pin "10") (pinfunction "10_10") (pintype "passive"))
    )
    (net (code "80") (name "/SD2Data4") (class "Default")
      (node (ref "SD2") (pin "4") (pinfunction "4_4") (pintype "passive"))
    )
    (net (code "81") (name "/SD2Data5") (class "Default")
      (node (ref "SD2") (pin "2") (pinfunction "2_2") (pintype "passive"))
    )
    (net (code "82") (name "/SD2Data6") (class "Default")
      (node (ref "SD2") (pin "33") (pinfunction "33_33") (pintype "passive"))
    )
    (net (code "83") (name "/SD2Data7") (class "Default")
      (node (ref "SD2") (pin "31") (pinfunction "31_31") (pintype "passive"))
    )
    (net (code "84") (name "/SD2reset") (class "Default")
      (node (ref "R2") (pin "1") (pinfunction "1_1") (pintype "passive"))
      (node (ref "SD2") (pin "12") (pinfunction "12_12") (pintype "passive"))
    )
    (net (code "85") (name "/SD3Clk") (class "Default")
      (node (ref "SD3") (pin "8") (pinfunction "8_8") (pintype "passive"))
    )
    (net (code "86") (name "/SD3Cmd") (class "Default")
      (node (ref "SD3") (pin "25") (pinfunction "25_25") (pintype "passive"))
    )
    (net (code "87") (name "/SD3Data0") (class "Default")
      (node (ref "SD3") (pin "6") (pinfunction "6_6") (pintype "passive"))
    )
    (net (code "88") (name "/SD3Data1") (class "Default")
      (node (ref "SD3") (pin "29") (pinfunction "29_29") (pintype "passive"))
    )
    (net (code "89") (name "/SD3Data2") (class "Default")
      (node (ref "SD3") (pin "27") (pinfunction "27_27") (pintype "passive"))
    )
    (net (code "90") (name "/SD3Data3") (class "Default")
      (node (ref "SD3") (pin "10") (pinfunction "10_10") (pintype "passive"))
    )
    (net (code "91") (name "/SD3Data4") (class "Default")
      (node (ref "SD3") (pin "4") (pinfunction "4_4") (pintype "passive"))
    )
    (net (code "92") (name "/SD3Data5") (class "Default")
      (node (ref "SD3") (pin "2") (pinfunction "2_2") (pintype "passive"))
    )
    (net (code "93") (name "/SD3Data6") (class "Default")
      (node (ref "SD3") (pin "33") (pinfunction "33_33") (pintype "passive"))
    )
    (net (code "94") (name "/SD3Data7") (class "Default")
      (node (ref "SD3") (pin "31") (pinfunction "31_31") (pintype "passive"))
    )
    (net (code "95") (name "/SD3reset") (class "Default")
      (node (ref "R3") (pin "1") (pinfunction "1_1") (pintype "passive"))
      (node (ref "SD3") (pin "12") (pinfunction "12_12") (pintype "passive"))
    )
    (net (code "96") (name "/SD4Clk") (class "Default")
      (node (ref "SD4") (pin "8") (pinfunction "8_8") (pintype "passive"))
    )
    (net (code "97") (name "/SD4Cmd") (class "Default")
      (node (ref "SD4") (pin "25") (pinfunction "25_25") (pintype "passive"))
    )
    (net (code "98") (name "/SD4Data0") (class "Default")
      (node (ref "SD4") (pin "6") (pinfunction "6_6") (pintype "passive"))
    )
    (net (code "99") (name "/SD4Data1") (class "Default")
      (node (ref "SD4") (pin "29") (pinfunction "29_29") (pintype "passive"))
    )
    (net (code "100") (name "/SD4Data2") (class "Default")
      (node (ref "SD4") (pin "27") (pinfunction "27_27") (pintype "passive"))
    )
    (net (code "101") (name "/SD4Data3") (class "Default")
      (node (ref "SD4") (pin "10") (pinfunction "10_10") (pintype "passive"))
    )
    (net (code "102") (name "/SD4Data4") (class "Default")
      (node (ref "SD4") (pin "4") (pinfunction "4_4") (pintype "passive"))
    )
    (net (code "103") (name "/SD4Data5") (class "Default")
      (node (ref "SD4") (pin "2") (pinfunction "2_2") (pintype "passive"))
    )
    (net (code "104") (name "/SD4Data6") (class "Default")
      (node (ref "SD4") (pin "33") (pinfunction "33_33") (pintype "passive"))
    )
    (net (code "105") (name "/SD4Data7") (class "Default")
      (node (ref "SD4") (pin "31") (pinfunction "31_31") (pintype "passive"))
    )
    (net (code "106") (name "/SD4reset") (class "Default")
      (node (ref "R4") (pin "1") (pinfunction "1_1") (pintype "passive"))
      (node (ref "SD4") (pin "12") (pinfunction "12_12") (pintype "passive"))
    )
    (net (code "107") (name "/SD5Clk") (class "Default")
      (node (ref "SD5") (pin "8") (pinfunction "8_8") (pintype "passive"))
    )
    (net (code "108") (name "/SD5Cmd") (class "Default")
      (node (ref "SD5") (pin "25") (pinfunction "25_25") (pintype "passive"))
    )
    (net (code "109") (name "/SD5Data0") (class "Default")
      (node (ref "SD5") (pin "6") (pinfunction "6_6") (pintype "passive"))
    )
    (net (code "110") (name "/SD5Data1") (class "Default")
      (node (ref "SD5") (pin "29") (pinfunction "29_29") (pintype "passive"))
    )
    (net (code "111") (name "/SD5Data2") (class "Default")
      (node (ref "SD5") (pin "27") (pinfunction "27_27") (pintype "passive"))
    )
    (net (code "112") (name "/SD5Data3") (class "Default")
      (node (ref "SD5") (pin "10") (pinfunction "10_10") (pintype "passive"))
    )
    (net (code "113") (name "/SD5Data4") (class "Default")
      (node (ref "SD5") (pin "4") (pinfunction "4_4") (pintype "passive"))
    )
    (net (code "114") (name "/SD5Data5") (class "Default")
      (node (ref "SD5") (pin "2") (pinfunction "2_2") (pintype "passive"))
    )
    (net (code "115") (name "/SD5Data6") (class "Default")
      (node (ref "SD5") (pin "33") (pinfunction "33_33") (pintype "passive"))
    )
    (net (code "116") (name "/SD5Data7") (class "Default")
      (node (ref "SD5") (pin "31") (pinfunction "31_31") (pintype "passive"))
    )
    (net (code "117") (name "/SD5reset") (class "Default")
      (node (ref "R5") (pin "1") (pinfunction "1_1") (pintype "passive"))
      (node (ref "SD5") (pin "12") (pinfunction "12_12") (pintype "passive"))
    )
    (net (code "118") (name "/SD6Clk") (class "Default")
      (node (ref "SD6") (pin "8") (pinfunction "8_8") (pintype "passive"))
    )
    (net (code "119") (name "/SD6Cmd") (class "Default")
      (node (ref "SD6") (pin "25") (pinfunction "25_25") (pintype "passive"))
    )
    (net (code "120") (name "/SD6Data0") (class "Default")
      (node (ref "SD6") (pin "6") (pinfunction "6_6") (pintype "passive"))
    )
    (net (code "121") (name "/SD6Data1") (class "Default")
      (node (ref "SD6") (pin "29") (pinfunction "29_29") (pintype "passive"))
    )
    (net (code "122") (name "/SD6Data2") (class "Default")
      (node (ref "SD6") (pin "27") (pinfunction "27_27") (pintype "passive"))
    )
    (net (code "123") (name "/SD6Data3") (class "Default")
      (node (ref "SD6") (pin "10") (pinfunction "10_10") (pintype "passive"))
    )
    (net (code "124") (name "/SD6Data4") (class "Default")
      (node (ref "SD6") (pin "4") (pinfunction "4_4") (pintype "passive"))
    )
    (net (code "125") (name "/SD6Data5") (class "Default")
      (node (ref "SD6") (pin "2") (pinfunction "2_2") (pintype "passive"))
    )
    (net (code "126") (name "/SD6Data6") (class "Default")
      (node (ref "SD6") (pin "33") (pinfunction "33_33") (pintype "passive"))
    )
    (net (code "127") (name "/SD6Data7") (class "Default")
      (node (ref "SD6") (pin "31") (pinfunction "31_31") (pintype "passive"))
    )
    (net (code "128") (name "/SD6reset") (class "Default")
      (node (ref "R6") (pin "1") (pinfunction "1_1") (pintype "passive"))
      (node (ref "SD6") (pin "12") (pinfunction "12_12") (pintype "passive"))
    )
    (net (code "129") (name "/SD7Clk") (class "Default")
      (node (ref "SD7") (pin "8") (pinfunction "8_8") (pintype "passive"))
    )
    (net (code "130") (name "/SD7Cmd") (class "Default")
      (node (ref "SD7") (pin "25") (pinfunction "25_25") (pintype "passive"))
    )
    (net (code "131") (name "/SD7Data0") (class "Default")
      (node (ref "SD7") (pin "6") (pinfunction "6_6") (pintype "passive"))
    )
    (net (code "132") (name "/SD7Data1") (class "Default")
      (node (ref "SD7") (pin "29") (pinfunction "29_29") (pintype "passive"))
    )
    (net (code "133") (name "/SD7Data2") (class "Default")
      (node (ref "SD7") (pin "27") (pinfunction "27_27") (pintype "passive"))
    )
    (net (code "134") (name "/SD7Data3") (class "Default")
      (node (ref "SD7") (pin "10") (pinfunction "10_10") (pintype "passive"))
    )
    (net (code "135") (name "/SD7Data4") (class "Default")
      (node (ref "SD7") (pin "4") (pinfunction "4_4") (pintype "passive"))
    )
    (net (code "136") (name "/SD7Data5") (class "Default")
      (node (ref "SD7") (pin "2") (pinfunction "2_2") (pintype "passive"))
    )
    (net (code "137") (name "/SD7Data6") (class "Default")
      (node (ref "SD7") (pin "33") (pinfunction "33_33") (pintype "passive"))
    )
    (net (code "138") (name "/SD7Data7") (class "Default")
      (node (ref "SD7") (pin "31") (pinfunction "31_31") (pintype "passive"))
    )
    (net (code "139") (name "/SD7reset") (class "Default")
      (node (ref "R7") (pin "1") (pinfunction "1_1") (pintype "passive"))
      (node (ref "SD7") (pin "12") (pinfunction "12_12") (pintype "passive"))
    )
    (net (code "140") (name "/SD8Clk") (class "Default")
      (node (ref "SD8") (pin "8") (pinfunction "8_8") (pintype "passive"))
    )
    (net (code "141") (name "/SD8Cmd") (class "Default")
      (node (ref "SD8") (pin "25") (pinfunction "25_25") (pintype "passive"))
    )
    (net (code "142") (name "/SD8Data0") (class "Default")
      (node (ref "SD8") (pin "6") (pinfunction "6_6") (pintype "passive"))
    )
    (net (code "143") (name "/SD8Data1") (class "Default")
      (node (ref "SD8") (pin "29") (pinfunction "29_29") (pintype "passive"))
    )
    (net (code "144") (name "/SD8Data2") (class "Default")
      (node (ref "SD8") (pin "27") (pinfunction "27_27") (pintype "passive"))
    )
    (net (code "145") (name "/SD8Data3") (class "Default")
      (node (ref "SD8") (pin "10") (pinfunction "10_10") (pintype "passive"))
    )
    (net (code "146") (name "/SD8Data4") (class "Default")
      (node (ref "SD8") (pin "4") (pinfunction "4_4") (pintype "passive"))
    )
    (net (code "147") (name "/SD8Data5") (class "Default")
      (node (ref "SD8") (pin "2") (pinfunction "2_2") (pintype "passive"))
    )
    (net (code "148") (name "/SD8Data6") (class "Default")
      (node (ref "SD8") (pin "33") (pinfunction "33_33") (pintype "passive"))
    )
    (net (code "149") (name "/SD8Data7") (class "Default")
      (node (ref "SD8") (pin "31") (pinfunction "31_31") (pintype "passive"))
    )
    (net (code "150") (name "/SD8reset") (class "Default")
      (node (ref "R8") (pin "1") (pinfunction "1_1") (pintype "passive"))
      (node (ref "SD8") (pin "12") (pinfunction "12_12") (pintype "passive"))
    )
    (net (code "151") (name "/SD9Clk") (class "Default")
      (node (ref "SD9") (pin "8") (pinfunction "8_8") (pintype "passive"))
    )
    (net (code "152") (name "/SD9Cmd") (class "Default")
      (node (ref "SD9") (pin "25") (pinfunction "25_25") (pintype "passive"))
    )
    (net (code "153") (name "/SD9Data0") (class "Default")
      (node (ref "SD9") (pin "6") (pinfunction "6_6") (pintype "passive"))
    )
    (net (code "154") (name "/SD9Data1") (class "Default")
      (node (ref "SD9") (pin "29") (pinfunction "29_29") (pintype "passive"))
    )
    (net (code "155") (name "/SD9Data2") (class "Default")
      (node (ref "SD9") (pin "27") (pinfunction "27_27") (pintype "passive"))
    )
    (net (code "156") (name "/SD9Data3") (class "Default")
      (node (ref "SD9") (pin "10") (pinfunction "10_10") (pintype "passive"))
    )
    (net (code "157") (name "/SD9Data4") (class "Default")
      (node (ref "SD9") (pin "4") (pinfunction "4_4") (pintype "passive"))
    )
    (net (code "158") (name "/SD9Data5") (class "Default")
      (node (ref "SD9") (pin "2") (pinfunction "2_2") (pintype "passive"))
    )
    (net (code "159") (name "/SD9Data6") (class "Default")
      (node (ref "SD9") (pin "33") (pinfunction "33_33") (pintype "passive"))
    )
    (net (code "160") (name "/SD9Data7") (class "Default")
      (node (ref "SD9") (pin "31") (pinfunction "31_31") (pintype "passive"))
    )
    (net (code "161") (name "/SD9reset") (class "Default")
      (node (ref "R9") (pin "1") (pinfunction "1_1") (pintype "passive"))
      (node (ref "SD9") (pin "12") (pinfunction "12_12") (pintype "passive"))
    )
    (net (code "162") (name "/SD10Clk") (class "Default")
      (node (ref "SD10") (pin "8") (pinfunction "8_8") (pintype "passive"))
    )
    (net (code "163") (name "/SD10Cmd") (class "Default")
      (node (ref "SD10") (pin "25") (pinfunction "25_25") (pintype "passive"))
    )
    (net (code "164") (name "/SD10Data0") (class "Default")
      (node (ref "SD10") (pin "6") (pinfunction "6_6") (pintype "passive"))
    )
    (net (code "165") (name "/SD10Data1") (class "Default")
      (node (ref "SD10") (pin "29") (pinfunction "29_29") (pintype "passive"))
    )
    (net (code "166") (name "/SD10Data2") (class "Default")
      (node (ref "SD10") (pin "27") (pinfunction "27_27") (pintype "passive"))
    )
    (net (code "167") (name "/SD10Data3") (class "Default")
      (node (ref "SD10") (pin "10") (pinfunction "10_10") (pintype "passive"))
    )
    (net (code "168") (name "/SD10Data4") (class "Default")
      (node (ref "SD10") (pin "4") (pinfunction "4_4") (pintype "passive"))
    )
    (net (code "169") (name "/SD10Data5") (class "Default")
      (node (ref "SD10") (pin "2") (pinfunction "2_2") (pintype "passive"))
    )
    (net (code "170") (name "/SD10Data6") (class "Default")
      (node (ref "SD10") (pin "33") (pinfunction "33_33") (pintype "passive"))
    )
    (net (code "171") (name "/SD10Data7") (class "Default")
      (node (ref "SD10") (pin "31") (pinfunction "31_31") (pintype "passive"))
    )
    (net (code "172") (name "/SD10reset") (class "Default")
      (node (ref "R10") (pin "1") (pinfunction "1_1") (pintype "passive"))
      (node (ref "SD10") (pin "12") (pinfunction "12_12") (pintype "passive"))
    )
    (net (code "173") (name "/SD11Clk") (class "Default")
      (node (ref "SD11") (pin "8") (pinfunction "8_8") (pintype "passive"))
    )
    (net (code "174") (name "/SD11Cmd") (class "Default")
      (node (ref "SD11") (pin "25") (pinfunction "25_25") (pintype "passive"))
    )
    (net (code "175") (name "/SD11Data0") (class "Default")
      (node (ref "SD11") (pin "6") (pinfunction "6_6") (pintype "passive"))
    )
    (net (code "176") (name "/SD11Data1") (class "Default")
      (node (ref "SD11") (pin "29") (pinfunction "29_29") (pintype "passive"))
    )
    (net (code "177") (name "/SD11Data2") (class "Default")
      (node (ref "SD11") (pin "27") (pinfunction "27_27") (pintype "passive"))
    )
    (net (code "178") (name "/SD11Data3") (class "Default")
      (node (ref "SD11") (pin "10") (pinfunction "10_10") (pintype "passive"))
    )
    (net (code "179") (name "/SD11Data4") (class "Default")
      (node (ref "SD11") (pin "4") (pinfunction "4_4") (pintype "passive"))
    )
    (net (code "180") (name "/SD11Data5") (class "Default")
      (node (ref "SD11") (pin "2") (pinfunction "2_2") (pintype "passive"))
    )
    (net (code "181") (name "/SD11Data6") (class "Default")
      (node (ref "SD11") (pin "33") (pinfunction "33_33") (pintype "passive"))
    )
    (net (code "182") (name "/SD11Data7") (class "Default")
      (node (ref "SD11") (pin "31") (pinfunction "31_31") (pintype "passive"))
    )
    (net (code "183") (name "/SD11reset") (class "Default")
      (node (ref "R11") (pin "1") (pinfunction "1_1") (pintype "passive"))
      (node (ref "SD11") (pin "12") (pinfunction "12_12") (pintype "passive"))
    )
    (net (code "184") (name "/SD12Clk") (class "Default")
      (node (ref "SD12") (pin "8") (pinfunction "8_8") (pintype "passive"))
    )
    (net (code "185") (name "/SD12Cmd") (class "Default")
      (node (ref "SD12") (pin "25") (pinfunction "25_25") (pintype "passive"))
    )
    (net (code "186") (name "/SD12Data0") (class "Default")
      (node (ref "SD12") (pin "6") (pinfunction "6_6") (pintype "passive"))
    )
    (net (code "187") (name "/SD12Data1") (class "Default")
      (node (ref "SD12") (pin "29") (pinfunction "29_29") (pintype "passive"))
    )
    (net (code "188") (name "/SD12Data2") (class "Default")
      (node (ref "SD12") (pin "27") (pinfunction "27_27") (pintype "passive"))
    )
    (net (code "189") (name "/SD12Data3") (class "Default")
      (node (ref "SD12") (pin "10") (pinfunction "10_10") (pintype "passive"))
    )
    (net (code "190") (name "/SD12Data4") (class "Default")
      (node (ref "SD12") (pin "4") (pinfunction "4_4") (pintype "passive"))
    )
    (net (code "191") (name "/SD12Data5") (class "Default")
      (node (ref "SD12") (pin "2") (pinfunction "2_2") (pintype "passive"))
    )
    (net (code "192") (name "/SD12Data6") (class "Default")
      (node (ref "SD12") (pin "33") (pinfunction "33_33") (pintype "passive"))
    )
    (net (code "193") (name "/SD12Data7") (class "Default")
      (node (ref "SD12") (pin "31") (pinfunction "31_31") (pintype "passive"))
    )
    (net (code "194") (name "/SD12reset") (class "Default")
      (node (ref "R12") (pin "1") (pinfunction "1_1") (pintype "passive"))
      (node (ref "SD12") (pin "12") (pinfunction "12_12") (pintype "passive"))
    )
    (net (code "195") (name "1V8") (class "Default")
      (node (ref "JM1") (pin "1") (pinfunction "1_1") (pintype "passive"))
    )
    (net (code "196") (name "3V3") (class "Default")
      (node (ref "C1") (pin "2") (pinfunction "2_2") (pintype "passive"))
      (node (ref "C10") (pin "2") (pinfunction "2_2") (pintype "passive"))
      (node (ref "C11") (pin "2") (pinfunction "2_2") (pintype "passive"))
      (node (ref "C12") (pin "2") (pinfunction "2_2") (pintype "passive"))
      (node (ref "C13") (pin "2") (pinfunction "2_2") (pintype "passive"))
      (node (ref "C14") (pin "2") (pinfunction "2_2") (pintype "passive"))
      (node (ref "C15") (pin "2") (pinfunction "2_2") (pintype "passive"))
      (node (ref "C16") (pin "2") (pinfunction "2_2") (pintype "passive"))
      (node (ref "C17") (pin "2") (pinfunction "2_2") (pintype "passive"))
      (node (ref "C18") (pin "2") (pinfunction "2_2") (pintype "passive"))
      (node (ref "C19") (pin "2") (pinfunction "2_2") (pintype "passive"))
      (node (ref "C2") (pin "2") (pinfunction "2_2") (pintype "passive"))
      (node (ref "C20") (pin "2") (pinfunction "2_2") (pintype "passive"))
      (node (ref "C21") (pin "2") (pinfunction "2_2") (pintype "passive"))
      (node (ref "C22") (pin "2") (pinfunction "2_2") (pintype "passive"))
      (node (ref "C23") (pin "2") (pinfunction "2_2") (pintype "passive"))
      (node (ref "C24") (pin "2") (pinfunction "2_2") (pintype "passive"))
      (node (ref "C3") (pin "2") (pinfunction "2_2") (pintype "passive"))
      (node (ref "C4") (pin "2") (pinfunction "2_2") (pintype "passive"))
      (node (ref "C5") (pin "2") (pinfunction "2_2") (pintype "passive"))
      (node (ref "C6") (pin "2") (pinfunction "2_2") (pintype "passive"))
      (node (ref "C7") (pin "2") (pinfunction "2_2") (pintype "passive"))
      (node (ref "C8") (pin "2") (pinfunction "2_2") (pintype "passive"))
      (node (ref "C9") (pin "2") (pinfunction "2_2") (pintype "passive"))
      (node (ref "JM1") (pin "3") (pinfunction "3_3") (pintype "passive"))
      (node (ref "R1") (pin "2") (pinfunction "2_2") (pintype "passive"))
      (node (ref "R10") (pin "2") (pinfunction "2_2") (pintype "passive"))
      (node (ref "R11") (pin "2") (pinfunction "2_2") (pintype "passive"))
      (node (ref "R12") (pin "2") (pinfunction "2_2") (pintype "passive"))
      (node (ref "R2") (pin "2") (pinfunction "2_2") (pintype "passive"))
      (node (ref "R3") (pin "2") (pinfunction "2_2") (pintype "passive"))
      (node (ref "R4") (pin "2") (pinfunction "2_2") (pintype "passive"))
      (node (ref "R5") (pin "2") (pinfunction "2_2") (pintype "passive"))
      (node (ref "R6") (pin "2") (pinfunction "2_2") (pintype "passive"))
      (node (ref "R7") (pin "2") (pinfunction "2_2") (pintype "passive"))
      (node (ref "R8") (pin "2") (pinfunction "2_2") (pintype "passive"))
      (node (ref "R9") (pin "2") (pinfunction "2_2") (pintype "passive"))
      (node (ref "SD1") (pin "20") (pinfunction "20_20") (pintype "passive"))
      (node (ref "SD1") (pin "21") (pinfunction "21_21") (pintype "passive"))
      (node (ref "SD1") (pin "22") (pinfunction "22_22") (pintype "passive"))
      (node (ref "SD1") (pin "23") (pinfunction "23_23") (pintype "passive"))
      (node (ref "SD10") (pin "20") (pinfunction "20_20") (pintype "passive"))
      (node (ref "SD10") (pin "21") (pinfunction "21_21") (pintype "passive"))
      (node (ref "SD10") (pin "22") (pinfunction "22_22") (pintype "passive"))
      (node (ref "SD10") (pin "23") (pinfunction "23_23") (pintype "passive"))
      (node (ref "SD11") (pin "20") (pinfunction "20_20") (pintype "passive"))
      (node (ref "SD11") (pin "21") (pinfunction "21_21") (pintype "passive"))
      (node (ref "SD11") (pin "22") (pinfunction "22_22") (pintype "passive"))
      (node (ref "SD11") (pin "23") (pinfunction "23_23") (pintype "passive"))
      (node (ref "SD12") (pin "20") (pinfunction "20_20") (pintype "passive"))
      (node (ref "SD12") (pin "21") (pinfunction "21_21") (pintype "passive"))
      (node (ref "SD12") (pin "22") (pinfunction "22_22") (pintype "passive"))
      (node (ref "SD12") (pin "23") (pinfunction "23_23") (pintype "passive"))
      (node (ref "SD2") (pin "20") (pinfunction "20_20") (pintype "passive"))
      (node (ref "SD2") (pin "21") (pinfunction "21_21") (pintype "passive"))
      (node (ref "SD2") (pin "22") (pinfunction "22_22") (pintype "passive"))
      (node (ref "SD2") (pin "23") (pinfunction "23_23") (pintype "passive"))
      (node (ref "SD3") (pin "20") (pinfunction "20_20") (pintype "passive"))
      (node (ref "SD3") (pin "21") (pinfunction "21_21") (pintype "passive"))
      (node (ref "SD3") (pin "22") (pinfunction "22_22") (pintype "passive"))
      (node (ref "SD3") (pin "23") (pinfunction "23_23") (pintype "passive"))
      (node (ref "SD4") (pin "20") (pinfunction "20_20") (pintype "passive"))
      (node (ref "SD4") (pin "21") (pinfunction "21_21") (pintype "passive"))
      (node (ref "SD4") (pin "22") (pinfunction "22_22") (pintype "passive"))
      (node (ref "SD4") (pin "23") (pinfunction "23_23") (pintype "passive"))
      (node (ref "SD5") (pin "20") (pinfunction "20_20") (pintype "passive"))
      (node (ref "SD5") (pin "21") (pinfunction "21_21") (pintype "passive"))
      (node (ref "SD5") (pin "22") (pinfunction "22_22") (pintype "passive"))
      (node (ref "SD5") (pin "23") (pinfunction "23_23") (pintype "passive"))
      (node (ref "SD6") (pin "20") (pinfunction "20_20") (pintype "passive"))
      (node (ref "SD6") (pin "21") (pinfunction "21_21") (pintype "passive"))
      (node (ref "SD6") (pin "22") (pinfunction "22_22") (pintype "passive"))
      (node (ref "SD6") (pin "23") (pinfunction "23_23") (pintype "passive"))
      (node (ref "SD7") (pin "20") (pinfunction "20_20") (pintype "passive"))
      (node (ref "SD7") (pin "21") (pinfunction "21_21") (pintype "passive"))
      (node (ref "SD7") (pin "22") (pinfunction "22_22") (pintype "passive"))
      (node (ref "SD7") (pin "23") (pinfunction "23_23") (pintype "passive"))
      (node (ref "SD8") (pin "20") (pinfunction "20_20") (pintype "passive"))
      (node (ref "SD8") (pin "21") (pinfunction "21_21") (pintype "passive"))
      (node (ref "SD8") (pin "22") (pinfunction "22_22") (pintype "passive"))
      (node (ref "SD8") (pin "23") (pinfunction "23_23") (pintype "passive"))
      (node (ref "SD9") (pin "20") (pinfunction "20_20") (pintype "passive"))
      (node (ref "SD9") (pin "21") (pinfunction "21_21") (pintype "passive"))
      (node (ref "SD9") (pin "22") (pinfunction "22_22") (pintype "passive"))
      (node (ref "SD9") (pin "23") (pinfunction "23_23") (pintype "passive"))
    )
    (net (code "197") (name "GND") (class "Default")
      (node (ref "C1") (pin "1") (pinfunction "1_1") (pintype "passive"))
      (node (ref "C10") (pin "1") (pinfunction "1_1") (pintype "passive"))
      (node (ref "C11") (pin "1") (pinfunction "1_1") (pintype "passive"))
      (node (ref "C12") (pin "1") (pinfunction "1_1") (pintype "passive"))
      (node (ref "C13") (pin "1") (pinfunction "1_1") (pintype "passive"))
      (node (ref "C14") (pin "1") (pinfunction "1_1") (pintype "passive"))
      (node (ref "C15") (pin "1") (pinfunction "1_1") (pintype "passive"))
      (node (ref "C16") (pin "1") (pinfunction "1_1") (pintype "passive"))
      (node (ref "C17") (pin "1") (pinfunction "1_1") (pintype "passive"))
      (node (ref "C18") (pin "1") (pinfunction "1_1") (pintype "passive"))
      (node (ref "C19") (pin "1") (pinfunction "1_1") (pintype "passive"))
      (node (ref "C2") (pin "1") (pinfunction "1_1") (pintype "passive"))
      (node (ref "C20") (pin "1") (pinfunction "1_1") (pintype "passive"))
      (node (ref "C21") (pin "1") (pinfunction "1_1") (pintype "passive"))
      (node (ref "C22") (pin "1") (pinfunction "1_1") (pintype "passive"))
      (node (ref "C23") (pin "1") (pinfunction "1_1") (pintype "passive"))
      (node (ref "C24") (pin "1") (pinfunction "1_1") (pintype "passive"))
      (node (ref "C3") (pin "1") (pinfunction "1_1") (pintype "passive"))
      (node (ref "C4") (pin "1") (pinfunction "1_1") (pintype "passive"))
      (node (ref "C5") (pin "1") (pinfunction "1_1") (pintype "passive"))
      (node (ref "C6") (pin "1") (pinfunction "1_1") (pintype "passive"))
      (node (ref "C7") (pin "1") (pinfunction "1_1") (pintype "passive"))
      (node (ref "C8") (pin "1") (pinfunction "1_1") (pintype "passive"))
      (node (ref "C9") (pin "1") (pinfunction "1_1") (pintype "passive"))
      (node (ref "P1") (pin "11") (pinfunction "11_11") (pintype "passive"))
      (node (ref "P1") (pin "12") (pinfunction "12_12") (pintype "passive"))
      (node (ref "P1") (pin "21") (pinfunction "21_21") (pintype "passive"))
      (node (ref "P1") (pin "22") (pinfunction "22_22") (pintype "passive"))
      (node (ref "P1") (pin "31") (pinfunction "31_31") (pintype "passive"))
      (node (ref "P1") (pin "32") (pinfunction "32_32") (pintype "passive"))
      (node (ref "P1") (pin "41") (pinfunction "41_41") (pintype "passive"))
      (node (ref "P1") (pin "42") (pinfunction "42_42") (pintype "passive"))
      (node (ref "P1") (pin "51") (pinfunction "51_51") (pintype "passive"))
      (node (ref "P1") (pin "52") (pinfunction "52_52") (pintype "passive"))
      (node (ref "P17") (pin "11") (pinfunction "11_11") (pintype "bidirectional"))
      (node (ref "P17") (pin "13") (pinfunction "13_13") (pintype "bidirectional"))
      (node (ref "P17") (pin "3") (pinfunction "3_3") (pintype "bidirectional"))
      (node (ref "P17") (pin "5") (pinfunction "5_5") (pintype "bidirectional"))
      (node (ref "P17") (pin "7") (pinfunction "7_7") (pintype "bidirectional"))
      (node (ref "P17") (pin "9") (pinfunction "9_9") (pintype "bidirectional"))
      (node (ref "P18") (pin "2") (pinfunction "2_2") (pintype "bidirectional"))
      (node (ref "P2") (pin "11") (pinfunction "11_11") (pintype "passive"))
      (node (ref "P2") (pin "12") (pinfunction "12_12") (pintype "passive"))
      (node (ref "P2") (pin "21") (pinfunction "21_21") (pintype "passive"))
      (node (ref "P2") (pin "22") (pinfunction "22_22") (pintype "passive"))
      (node (ref "P2") (pin "31") (pinfunction "31_31") (pintype "passive"))
      (node (ref "P2") (pin "32") (pinfunction "32_32") (pintype "passive"))
      (node (ref "P2") (pin "41") (pinfunction "41_41") (pintype "passive"))
      (node (ref "P2") (pin "42") (pinfunction "42_42") (pintype "passive"))
      (node (ref "P2") (pin "51") (pinfunction "51_51") (pintype "passive"))
      (node (ref "P2") (pin "52") (pinfunction "52_52") (pintype "passive"))
      (node (ref "P3") (pin "11") (pinfunction "11_11") (pintype "passive"))
      (node (ref "P3") (pin "12") (pinfunction "12_12") (pintype "passive"))
      (node (ref "P3") (pin "21") (pinfunction "21_21") (pintype "passive"))
      (node (ref "P3") (pin "22") (pinfunction "22_22") (pintype "passive"))
      (node (ref "P3") (pin "31") (pinfunction "31_31") (pintype "passive"))
      (node (ref "P3") (pin "32") (pinfunction "32_32") (pintype "passive"))
      (node (ref "P3") (pin "35") (pinfunction "35_35") (pintype "passive"))
      (node (ref "P3") (pin "36") (pinfunction "36_36") (pintype "passive"))
      (node (ref "P3") (pin "41") (pinfunction "41_41") (pintype "passive"))
      (node (ref "P3") (pin "42") (pinfunction "42_42") (pintype "passive"))
      (node (ref "P3") (pin "51") (pinfunction "51_51") (pintype "passive"))
      (node (ref "P3") (pin "52") (pinfunction "52_52") (pintype "passive"))
      (node (ref "P4") (pin "11") (pinfunction "11_11") (pintype "passive"))
      (node (ref "P4") (pin "12") (pinfunction "12_12") (pintype "passive"))
      (node (ref "P4") (pin "21") (pinfunction "21_21") (pintype "passive"))
      (node (ref "P4") (pin "22") (pinfunction "22_22") (pintype "passive"))
      (node (ref "P4") (pin "31") (pinfunction "31_31") (pintype "passive"))
      (node (ref "P4") (pin "32") (pinfunction "32_32") (pintype "passive"))
      (node (ref "P4") (pin "41") (pinfunction "41_41") (pintype "passive"))
      (node (ref "P4") (pin "42") (pinfunction "42_42") (pintype "passive"))
      (node (ref "P4") (pin "51") (pinfunction "51_51") (pintype "passive"))
      (node (ref "P4") (pin "52") (pinfunction "52_52") (pintype "passive"))
      (node (ref "SD1") (pin "1") (pinfunction "1_1") (pintype "passive"))
      (node (ref "SD1") (pin "11") (pinfunction "11_11") (pintype "passive"))
      (node (ref "SD1") (pin "13") (pinfunction "13_13") (pintype "passive"))
      (node (ref "SD1") (pin "14") (pinfunction "14_14") (pintype "passive"))
      (node (ref "SD1") (pin "16") (pinfunction "16_16") (pintype "passive"))
      (node (ref "SD1") (pin "17") (pinfunction "17_17") (pintype "passive"))
      (node (ref "SD1") (pin "18") (pinfunction "18_18") (pintype "passive"))
      (node (ref "SD1") (pin "19") (pinfunction "19_19") (pintype "passive"))
      (node (ref "SD1") (pin "24") (pinfunction "24_24") (pintype "passive"))
      (node (ref "SD1") (pin "26") (pinfunction "26_26") (pintype "passive"))
      (node (ref "SD1") (pin "28") (pinfunction "28_28") (pintype "passive"))
      (node (ref "SD1") (pin "3") (pinfunction "3_3") (pintype "passive"))
      (node (ref "SD1") (pin "30") (pinfunction "30_30") (pintype "passive"))
      (node (ref "SD1") (pin "32") (pinfunction "32_32") (pintype "passive"))
      (node (ref "SD1") (pin "34") (pinfunction "34_34") (pintype "passive"))
      (node (ref "SD1") (pin "5") (pinfunction "5_5") (pintype "passive"))
      (node (ref "SD1") (pin "7") (pinfunction "7_7") (pintype "passive"))
      (node (ref "SD1") (pin "9") (pinfunction "9_9") (pintype "passive"))
      (node (ref "SD10") (pin "1") (pinfunction "1_1") (pintype "passive"))
      (node (ref "SD10") (pin "11") (pinfunction "11_11") (pintype "passive"))
      (node (ref "SD10") (pin "13") (pinfunction "13_13") (pintype "passive"))
      (node (ref "SD10") (pin "14") (pinfunction "14_14") (pintype "passive"))
      (node (ref "SD10") (pin "16") (pinfunction "16_16") (pintype "passive"))
      (node (ref "SD10") (pin "17") (pinfunction "17_17") (pintype "passive"))
      (node (ref "SD10") (pin "18") (pinfunction "18_18") (pintype "passive"))
      (node (ref "SD10") (pin "19") (pinfunction "19_19") (pintype "passive"))
      (node (ref "SD10") (pin "24") (pinfunction "24_24") (pintype "passive"))
      (node (ref "SD10") (pin "26") (pinfunction "26_26") (pintype "passive"))
      (node (ref "SD10") (pin "28") (pinfunction "28_28") (pintype "passive"))
      (node (ref "SD10") (pin "3") (pinfunction "3_3") (pintype "passive"))
      (node (ref "SD10") (pin "30") (pinfunction "30_30") (pintype "passive"))
      (node (ref "SD10") (pin "32") (pinfunction "32_32") (pintype "passive"))
      (node (ref "SD10") (pin "34") (pinfunction "34_34") (pintype "passive"))
      (node (ref "SD10") (pin "5") (pinfunction "5_5") (pintype "passive"))
      (node (ref "SD10") (pin "7") (pinfunction "7_7") (pintype "passive"))
      (node (ref "SD10") (pin "9") (pinfunction "9_9") (pintype "passive"))
      (node (ref "SD11") (pin "1") (pinfunction "1_1") (pintype "passive"))
      (node (ref "SD11") (pin "11") (pinfunction "11_11") (pintype "passive"))
      (node (ref "SD11") (pin "13") (pinfunction "13_13") (pintype "passive"))
      (node (ref "SD11") (pin "14") (pinfunction "14_14") (pintype "passive"))
      (node (ref "SD11") (pin "16") (pinfunction "16_16") (pintype "passive"))
      (node (ref "SD11") (pin "17") (pinfunction "17_17") (pintype "passive"))
      (node (ref "SD11") (pin "18") (pinfunction "18_18") (pintype "passive"))
      (node (ref "SD11") (pin "19") (pinfunction "19_19") (pintype "passive"))
      (node (ref "SD11") (pin "24") (pinfunction "24_24") (pintype "passive"))
      (node (ref "SD11") (pin "26") (pinfunction "26_26") (pintype "passive"))
      (node (ref "SD11") (pin "28") (pinfunction "28_28") (pintype "passive"))
      (node (ref "SD11") (pin "3") (pinfunction "3_3") (pintype "passive"))
      (node (ref "SD11") (pin "30") (pinfunction "30_30") (pintype "passive"))
      (node (ref "SD11") (pin "32") (pinfunction "32_32") (pintype "passive"))
      (node (ref "SD11") (pin "34") (pinfunction "34_34") (pintype "passive"))
      (node (ref "SD11") (pin "5") (pinfunction "5_5") (pintype "passive"))
      (node (ref "SD11") (pin "7") (pinfunction "7_7") (pintype "passive"))
      (node (ref "SD11") (pin "9") (pinfunction "9_9") (pintype "passive"))
      (node (ref "SD12") (pin "1") (pinfunction "1_1") (pintype "passive"))
      (node (ref "SD12") (pin "11") (pinfunction "11_11") (pintype "passive"))
      (node (ref "SD12") (pin "13") (pinfunction "13_13") (pintype "passive"))
      (node (ref "SD12") (pin "14") (pinfunction "14_14") (pintype "passive"))
      (node (ref "SD12") (pin "16") (pinfunction "16_16") (pintype "passive"))
      (node (ref "SD12") (pin "17") (pinfunction "17_17") (pintype "passive"))
      (node (ref "SD12") (pin "18") (pinfunction "18_18") (pintype "passive"))
      (node (ref "SD12") (pin "19") (pinfunction "19_19") (pintype "passive"))
      (node (ref "SD12") (pin "24") (pinfunction "24_24") (pintype "passive"))
      (node (ref "SD12") (pin "26") (pinfunction "26_26") (pintype "passive"))
      (node (ref "SD12") (pin "28") (pinfunction "28_28") (pintype "passive"))
      (node (ref "SD12") (pin "3") (pinfunction "3_3") (pintype "passive"))
      (node (ref "SD12") (pin "30") (pinfunction "30_30") (pintype "passive"))
      (node (ref "SD12") (pin "32") (pinfunction "32_32") (pintype "passive"))
      (node (ref "SD12") (pin "34") (pinfunction "34_34") (pintype "passive"))
      (node (ref "SD12") (pin "5") (pinfunction "5_5") (pintype "passive"))
      (node (ref "SD12") (pin "7") (pinfunction "7_7") (pintype "passive"))
      (node (ref "SD12") (pin "9") (pinfunction "9_9") (pintype "passive"))
      (node (ref "SD2") (pin "1") (pinfunction "1_1") (pintype "passive"))
      (node (ref "SD2") (pin "11") (pinfunction "11_11") (pintype "passive"))
      (node (ref "SD2") (pin "13") (pinfunction "13_13") (pintype "passive"))
      (node (ref "SD2") (pin "14") (pinfunction "14_14") (pintype "passive"))
      (node (ref "SD2") (pin "16") (pinfunction "16_16") (pintype "passive"))
      (node (ref "SD2") (pin "17") (pinfunction "17_17") (pintype "passive"))
      (node (ref "SD2") (pin "18") (pinfunction "18_18") (pintype "passive"))
      (node (ref "SD2") (pin "19") (pinfunction "19_19") (pintype "passive"))
      (node (ref "SD2") (pin "24") (pinfunction "24_24") (pintype "passive"))
      (node (ref "SD2") (pin "26") (pinfunction "26_26") (pintype "passive"))
      (node (ref "SD2") (pin "28") (pinfunction "28_28") (pintype "passive"))
      (node (ref "SD2") (pin "3") (pinfunction "3_3") (pintype "passive"))
      (node (ref "SD2") (pin "30") (pinfunction "30_30") (pintype "passive"))
      (node (ref "SD2") (pin "32") (pinfunction "32_32") (pintype "passive"))
      (node (ref "SD2") (pin "34") (pinfunction "34_34") (pintype "passive"))
      (node (ref "SD2") (pin "5") (pinfunction "5_5") (pintype "passive"))
      (node (ref "SD2") (pin "7") (pinfunction "7_7") (pintype "passive"))
      (node (ref "SD2") (pin "9") (pinfunction "9_9") (pintype "passive"))
      (node (ref "SD3") (pin "1") (pinfunction "1_1") (pintype "passive"))
      (node (ref "SD3") (pin "11") (pinfunction "11_11") (pintype "passive"))
      (node (ref "SD3") (pin "13") (pinfunction "13_13") (pintype "passive"))
      (node (ref "SD3") (pin "14") (pinfunction "14_14") (pintype "passive"))
      (node (ref "SD3") (pin "16") (pinfunction "16_16") (pintype "passive"))
      (node (ref "SD3") (pin "17") (pinfunction "17_17") (pintype "passive"))
      (node (ref "SD3") (pin "18") (pinfunction "18_18") (pintype "passive"))
      (node (ref "SD3") (pin "19") (pinfunction "19_19") (pintype "passive"))
      (node (ref "SD3") (pin "24") (pinfunction "24_24") (pintype "passive"))
      (node (ref "SD3") (pin "26") (pinfunction "26_26") (pintype "passive"))
      (node (ref "SD3") (pin "28") (pinfunction "28_28") (pintype "passive"))
      (node (ref "SD3") (pin "3") (pinfunction "3_3") (pintype "passive"))
      (node (ref "SD3") (pin "30") (pinfunction "30_30") (pintype "passive"))
      (node (ref "SD3") (pin "32") (pinfunction "32_32") (pintype "passive"))
      (node (ref "SD3") (pin "34") (pinfunction "34_34") (pintype "passive"))
      (node (ref "SD3") (pin "5") (pinfunction "5_5") (pintype "passive"))
      (node (ref "SD3") (pin "7") (pinfunction "7_7") (pintype "passive"))
      (node (ref "SD3") (pin "9") (pinfunction "9_9") (pintype "passive"))
      (node (ref "SD4") (pin "1") (pinfunction "1_1") (pintype "passive"))
      (node (ref "SD4") (pin "11") (pinfunction "11_11") (pintype "passive"))
      (node (ref "SD4") (pin "13") (pinfunction "13_13") (pintype "passive"))
      (node (ref "SD4") (pin "14") (pinfunction "14_14") (pintype "passive"))
      (node (ref "SD4") (pin "16") (pinfunction "16_16") (pintype "passive"))
      (node (ref "SD4") (pin "17") (pinfunction "17_17") (pintype "passive"))
      (node (ref "SD4") (pin "18") (pinfunction "18_18") (pintype "passive"))
      (node (ref "SD4") (pin "19") (pinfunction "19_19") (pintype "passive"))
      (node (ref "SD4") (pin "24") (pinfunction "24_24") (pintype "passive"))
      (node (ref "SD4") (pin "26") (pinfunction "26_26") (pintype "passive"))
      (node (ref "SD4") (pin "28") (pinfunction "28_28") (pintype "passive"))
      (node (ref "SD4") (pin "3") (pinfunction "3_3") (pintype "passive"))
      (node (ref "SD4") (pin "30") (pinfunction "30_30") (pintype "passive"))
      (node (ref "SD4") (pin "32") (pinfunction "32_32") (pintype "passive"))
      (node (ref "SD4") (pin "34") (pinfunction "34_34") (pintype "passive"))
      (node (ref "SD4") (pin "5") (pinfunction "5_5") (pintype "passive"))
      (node (ref "SD4") (pin "7") (pinfunction "7_7") (pintype "passive"))
      (node (ref "SD4") (pin "9") (pinfunction "9_9") (pintype "passive"))
      (node (ref "SD5") (pin "1") (pinfunction "1_1") (pintype "passive"))
      (node (ref "SD5") (pin "11") (pinfunction "11_11") (pintype "passive"))
      (node (ref "SD5") (pin "13") (pinfunction "13_13") (pintype "passive"))
      (node (ref "SD5") (pin "14") (pinfunction "14_14") (pintype "passive"))
      (node (ref "SD5") (pin "16") (pinfunction "16_16") (pintype "passive"))
      (node (ref "SD5") (pin "17") (pinfunction "17_17") (pintype "passive"))
      (node (ref "SD5") (pin "18") (pinfunction "18_18") (pintype "passive"))
      (node (ref "SD5") (pin "19") (pinfunction "19_19") (pintype "passive"))
      (node (ref "SD5") (pin "24") (pinfunction "24_24") (pintype "passive"))
      (node (ref "SD5") (pin "26") (pinfunction "26_26") (pintype "passive"))
      (node (ref "SD5") (pin "28") (pinfunction "28_28") (pintype "passive"))
      (node (ref "SD5") (pin "3") (pinfunction "3_3") (pintype "passive"))
      (node (ref "SD5") (pin "30") (pinfunction "30_30") (pintype "passive"))
      (node (ref "SD5") (pin "32") (pinfunction "32_32") (pintype "passive"))
      (node (ref "SD5") (pin "34") (pinfunction "34_34") (pintype "passive"))
      (node (ref "SD5") (pin "5") (pinfunction "5_5") (pintype "passive"))
      (node (ref "SD5") (pin "7") (pinfunction "7_7") (pintype "passive"))
      (node (ref "SD5") (pin "9") (pinfunction "9_9") (pintype "passive"))
      (node (ref "SD6") (pin "1") (pinfunction "1_1") (pintype "passive"))
      (node (ref "SD6") (pin "11") (pinfunction "11_11") (pintype "passive"))
      (node (ref "SD6") (pin "13") (pinfunction "13_13") (pintype "passive"))
      (node (ref "SD6") (pin "14") (pinfunction "14_14") (pintype "passive"))
      (node (ref "SD6") (pin "16") (pinfunction "16_16") (pintype "passive"))
      (node (ref "SD6") (pin "17") (pinfunction "17_17") (pintype "passive"))
      (node (ref "SD6") (pin "18") (pinfunction "18_18") (pintype "passive"))
      (node (ref "SD6") (pin "19") (pinfunction "19_19") (pintype "passive"))
      (node (ref "SD6") (pin "24") (pinfunction "24_24") (pintype "passive"))
      (node (ref "SD6") (pin "26") (pinfunction "26_26") (pintype "passive"))
      (node (ref "SD6") (pin "28") (pinfunction "28_28") (pintype "passive"))
      (node (ref "SD6") (pin "3") (pinfunction "3_3") (pintype "passive"))
      (node (ref "SD6") (pin "30") (pinfunction "30_30") (pintype "passive"))
      (node (ref "SD6") (pin "32") (pinfunction "32_32") (pintype "passive"))
      (node (ref "SD6") (pin "34") (pinfunction "34_34") (pintype "passive"))
      (node (ref "SD6") (pin "5") (pinfunction "5_5") (pintype "passive"))
      (node (ref "SD6") (pin "7") (pinfunction "7_7") (pintype "passive"))
      (node (ref "SD6") (pin "9") (pinfunction "9_9") (pintype "passive"))
      (node (ref "SD7") (pin "1") (pinfunction "1_1") (pintype "passive"))
      (node (ref "SD7") (pin "11") (pinfunction "11_11") (pintype "passive"))
      (node (ref "SD7") (pin "13") (pinfunction "13_13") (pintype "passive"))
      (node (ref "SD7") (pin "14") (pinfunction "14_14") (pintype "passive"))
      (node (ref "SD7") (pin "16") (pinfunction "16_16") (pintype "passive"))
      (node (ref "SD7") (pin "17") (pinfunction "17_17") (pintype "passive"))
      (node (ref "SD7") (pin "18") (pinfunction "18_18") (pintype "passive"))
      (node (ref "SD7") (pin "19") (pinfunction "19_19") (pintype "passive"))
      (node (ref "SD7") (pin "24") (pinfunction "24_24") (pintype "passive"))
      (node (ref "SD7") (pin "26") (pinfunction "26_26") (pintype "passive"))
      (node (ref "SD7") (pin "28") (pinfunction "28_28") (pintype "passive"))
      (node (ref "SD7") (pin "3") (pinfunction "3_3") (pintype "passive"))
      (node (ref "SD7") (pin "30") (pinfunction "30_30") (pintype "passive"))
      (node (ref "SD7") (pin "32") (pinfunction "32_32") (pintype "passive"))
      (node (ref "SD7") (pin "34") (pinfunction "34_34") (pintype "passive"))
      (node (ref "SD7") (pin "5") (pinfunction "5_5") (pintype "passive"))
      (node (ref "SD7") (pin "7") (pinfunction "7_7") (pintype "passive"))
      (node (ref "SD7") (pin "9") (pinfunction "9_9") (pintype "passive"))
      (node (ref "SD8") (pin "1") (pinfunction "1_1") (pintype "passive"))
      (node (ref "SD8") (pin "11") (pinfunction "11_11") (pintype "passive"))
      (node (ref "SD8") (pin "13") (pinfunction "13_13") (pintype "passive"))
      (node (ref "SD8") (pin "14") (pinfunction "14_14") (pintype "passive"))
      (node (ref "SD8") (pin "16") (pinfunction "16_16") (pintype "passive"))
      (node (ref "SD8") (pin "17") (pinfunction "17_17") (pintype "passive"))
      (node (ref "SD8") (pin "18") (pinfunction "18_18") (pintype "passive"))
      (node (ref "SD8") (pin "19") (pinfunction "19_19") (pintype "passive"))
      (node (ref "SD8") (pin "24") (pinfunction "24_24") (pintype "passive"))
      (node (ref "SD8") (pin "26") (pinfunction "26_26") (pintype "passive"))
      (node (ref "SD8") (pin "28") (pinfunction "28_28") (pintype "passive"))
      (node (ref "SD8") (pin "3") (pinfunction "3_3") (pintype "passive"))
      (node (ref "SD8") (pin "30") (pinfunction "30_30") (pintype "passive"))
      (node (ref "SD8") (pin "32") (pinfunction "32_32") (pintype "passive"))
      (node (ref "SD8") (pin "34") (pinfunction "34_34") (pintype "passive"))
      (node (ref "SD8") (pin "5") (pinfunction "5_5") (pintype "passive"))
      (node (ref "SD8") (pin "7") (pinfunction "7_7") (pintype "passive"))
      (node (ref "SD8") (pin "9") (pinfunction "9_9") (pintype "passive"))
      (node (ref "SD9") (pin "1") (pinfunction "1_1") (pintype "passive"))
      (node (ref "SD9") (pin "11") (pinfunction "11_11") (pintype "passive"))
      (node (ref "SD9") (pin "13") (pinfunction "13_13") (pintype "passive"))
      (node (ref "SD9") (pin "14") (pinfunction "14_14") (pintype "passive"))
      (node (ref "SD9") (pin "16") (pinfunction "16_16") (pintype "passive"))
      (node (ref "SD9") (pin "17") (pinfunction "17_17") (pintype "passive"))
      (node (ref "SD9") (pin "18") (pinfunction "18_18") (pintype "passive"))
      (node (ref "SD9") (pin "19") (pinfunction "19_19") (pintype "passive"))
      (node (ref "SD9") (pin "24") (pinfunction "24_24") (pintype "passive"))
      (node (ref "SD9") (pin "26") (pinfunction "26_26") (pintype "passive"))
      (node (ref "SD9") (pin "28") (pinfunction "28_28") (pintype "passive"))
      (node (ref "SD9") (pin "3") (pinfunction "3_3") (pintype "passive"))
      (node (ref "SD9") (pin "30") (pinfunction "30_30") (pintype "passive"))
      (node (ref "SD9") (pin "32") (pinfunction "32_32") (pintype "passive"))
      (node (ref "SD9") (pin "34") (pinfunction "34_34") (pintype "passive"))
      (node (ref "SD9") (pin "5") (pinfunction "5_5") (pintype "passive"))
      (node (ref "SD9") (pin "7") (pinfunction "7_7") (pintype "passive"))
      (node (ref "SD9") (pin "9") (pinfunction "9_9") (pintype "passive"))
    )
    (net (code "198") (name "Net-(JM1-Pad2)") (class "Default")
      (node (ref "JM1") (pin "2") (pinfunction "2_2") (pintype "passive"))
      (node (ref "P17") (pin "2") (pinfunction "2_2") (pintype "bidirectional"))
    )
    (net (code "199") (name "Net-(P17-Pad4)") (class "Default")
      (node (ref "P17") (pin "4") (pinfunction "4_4") (pintype "bidirectional"))
      (node (ref "R34") (pin "2") (pinfunction "2_2") (pintype "passive"))
    )
    (net (code "200") (name "Net-(P17-Pad6)") (class "Default")
      (node (ref "P17") (pin "6") (pinfunction "6_6") (pintype "bidirectional"))
      (node (ref "R35") (pin "2") (pinfunction "2_2") (pintype "passive"))
    )
    (net (code "201") (name "Net-(P17-Pad8)") (class "Default")
      (node (ref "P17") (pin "8") (pinfunction "8_8") (pintype "bidirectional"))
      (node (ref "R36") (pin "2") (pinfunction "2_2") (pintype "passive"))
    )
    (net (code "202") (name "Net-(P17-Pad10)") (class "Default")
      (node (ref "P17") (pin "10") (pinfunction "10_10") (pintype "bidirectional"))
      (node (ref "R37") (pin "2") (pinfunction "2_2") (pintype "passive"))
    )
    (net (code "203") (name "VDDGPIO") (class "Default")
      (node (ref "P1") (pin "1") (pinfunction "1_1") (pintype "passive"))
      (node (ref "P1") (pin "2") (pinfunction "2_2") (pintype "passive"))
    )
    (net (code "204") (name "Vin") (class "Default")
      (node (ref "P18") (pin "1") (pinfunction "1_1") (pintype "bidirectional"))
    )
    (net (code "205") (name "unconnected-(P1-Pad58)") (class "Default")
      (node (ref "P1") (pin "58") (pinfunction "58_58") (pintype "passive"))
    )
    (net (code "206") (name "unconnected-(P1-Pad60)") (class "Default")
      (node (ref "P1") (pin "60") (pinfunction "60_60") (pintype "passive"))
    )
    (net (code "207") (name "unconnected-(P1-PadHOLE)") (class "Default")
      (node (ref "P1") (pin "HOLE") (pinfunction "HOLE_HOLE") (pintype "passive"))
    )
    (net (code "208") (name "unconnected-(P2-Pad1)") (class "Default")
      (node (ref "P2") (pin "1") (pinfunction "1_1") (pintype "passive"))
    )
    (net (code "209") (name "unconnected-(P2-Pad2)") (class "Default")
      (node (ref "P2") (pin "2") (pinfunction "2_2") (pintype "passive"))
    )
    (net (code "210") (name "unconnected-(P2-Pad3)") (class "Default")
      (node (ref "P2") (pin "3") (pinfunction "3_3") (pintype "passive"))
    )
    (net (code "211") (name "unconnected-(P2-Pad4)") (class "Default")
      (node (ref "P2") (pin "4") (pinfunction "4_4") (pintype "passive"))
    )
    (net (code "212") (name "unconnected-(P2-Pad5)") (class "Default")
      (node (ref "P2") (pin "5") (pinfunction "5_5") (pintype "passive"))
    )
    (net (code "213") (name "unconnected-(P2-Pad6)") (class "Default")
      (node (ref "P2") (pin "6") (pinfunction "6_6") (pintype "passive"))
    )
    (net (code "214") (name "unconnected-(P2-Pad7)") (class "Default")
      (node (ref "P2") (pin "7") (pinfunction "7_7") (pintype "passive"))
    )
    (net (code "215") (name "unconnected-(P2-Pad8)") (class "Default")
      (node (ref "P2") (pin "8") (pinfunction "8_8") (pintype "passive"))
    )
    (net (code "216") (name "unconnected-(P2-Pad9)") (class "Default")
      (node (ref "P2") (pin "9") (pinfunction "9_9") (pintype "passive"))
    )
    (net (code "217") (name "unconnected-(P2-Pad10)") (class "Default")
      (node (ref "P2") (pin "10") (pinfunction "10_10") (pintype "passive"))
    )
    (net (code "218") (name "unconnected-(P2-Pad13)") (class "Default")
      (node (ref "P2") (pin "13") (pinfunction "13_13") (pintype "passive"))
    )
    (net (code "219") (name "unconnected-(P2-Pad14)") (class "Default")
      (node (ref "P2") (pin "14") (pinfunction "14_14") (pintype "passive"))
    )
    (net (code "220") (name "unconnected-(P2-Pad15)") (class "Default")
      (node (ref "P2") (pin "15") (pinfunction "15_15") (pintype "passive"))
    )
    (net (code "221") (name "unconnected-(P2-Pad16)") (class "Default")
      (node (ref "P2") (pin "16") (pinfunction "16_16") (pintype "passive"))
    )
    (net (code "222") (name "unconnected-(P2-Pad17)") (class "Default")
      (node (ref "P2") (pin "17") (pinfunction "17_17") (pintype "passive"))
    )
    (net (code "223") (name "unconnected-(P2-Pad18)") (class "Default")
      (node (ref "P2") (pin "18") (pinfunction "18_18") (pintype "passive"))
    )
    (net (code "224") (name "unconnected-(P2-Pad19)") (class "Default")
      (node (ref "P2") (pin "19") (pinfunction "19_19") (pintype "passive"))
    )
    (net (code "225") (name "unconnected-(P2-Pad20)") (class "Default")
      (node (ref "P2") (pin "20") (pinfunction "20_20") (pintype "passive"))
    )
    (net (code "226") (name "unconnected-(P2-Pad23)") (class "Default")
      (node (ref "P2") (pin "23") (pinfunction "23_23") (pintype "passive"))
    )
    (net (code "227") (name "unconnected-(P2-Pad24)") (class "Default")
      (node (ref "P2") (pin "24") (pinfunction "24_24") (pintype "passive"))
    )
    (net (code "228") (name "unconnected-(P2-Pad25)") (class "Default")
      (node (ref "P2") (pin "25") (pinfunction "25_25") (pintype "passive"))
    )
    (net (code "229") (name "unconnected-(P2-Pad26)") (class "Default")
      (node (ref "P2") (pin "26") (pinfunction "26_26") (pintype "passive"))
    )
    (net (code "230") (name "unconnected-(P2-Pad27)") (class "Default")
      (node (ref "P2") (pin "27") (pinfunction "27_27") (pintype "passive"))
    )
    (net (code "231") (name "unconnected-(P2-Pad28)") (class "Default")
      (node (ref "P2") (pin "28") (pinfunction "28_28") (pintype "passive"))
    )
    (net (code "232") (name "unconnected-(P2-Pad29)") (class "Default")
      (node (ref "P2") (pin "29") (pinfunction "29_29") (pintype "passive"))
    )
    (net (code "233") (name "unconnected-(P2-Pad30)") (class "Default")
      (node (ref "P2") (pin "30") (pinfunction "30_30") (pintype "passive"))
    )
    (net (code "234") (name "unconnected-(P2-Pad33)") (class "Default")
      (node (ref "P2") (pin "33") (pinfunction "33_33") (pintype "passive"))
    )
    (net (code "235") (name "unconnected-(P2-Pad34)") (class "Default")
      (node (ref "P2") (pin "34") (pinfunction "34_34") (pintype "passive"))
    )
    (net (code "236") (name "unconnected-(P2-Pad35)") (class "Default")
      (node (ref "P2") (pin "35") (pinfunction "35_35") (pintype "passive"))
    )
    (net (code "237") (name "unconnected-(P2-Pad36)") (class "Default")
      (node (ref "P2") (pin "36") (pinfunction "36_36") (pintype "passive"))
    )
    (net (code "238") (name "unconnected-(P2-Pad37)") (class "Default")
      (node (ref "P2") (pin "37") (pinfunction "37_37") (pintype "passive"))
    )
    (net (code "239") (name "unconnected-(P2-Pad38)") (class "Default")
      (node (ref "P2") (pin "38") (pinfunction "38_38") (pintype "passive"))
    )
    (net (code "240") (name "unconnected-(P2-Pad39)") (class "Default")
      (node (ref "P2") (pin "39") (pinfunction "39_39") (pintype "passive"))
    )
    (net (code "241") (name "unconnected-(P2-Pad40)") (class "Default")
      (node (ref "P2") (pin "40") (pinfunction "40_40") (pintype "passive"))
    )
    (net (code "242") (name "unconnected-(P2-Pad43)") (class "Default")
      (node (ref "P2") (pin "43") (pinfunction "43_43") (pintype "passive"))
    )
    (net (code "243") (name "unconnected-(P2-Pad44)") (class "Default")
      (node (ref "P2") (pin "44") (pinfunction "44_44") (pintype "passive"))
    )
    (net (code "244") (name "unconnected-(P2-Pad45)") (class "Default")
      (node (ref "P2") (pin "45") (pinfunction "45_45") (pintype "passive"))
    )
    (net (code "245") (name "unconnected-(P2-Pad46)") (class "Default")
      (node (ref "P2") (pin "46") (pinfunction "46_46") (pintype "passive"))
    )
    (net (code "246") (name "unconnected-(P2-Pad47)") (class "Default")
      (node (ref "P2") (pin "47") (pinfunction "47_47") (pintype "passive"))
    )
    (net (code "247") (name "unconnected-(P2-Pad48)") (class "Default")
      (node (ref "P2") (pin "48") (pinfunction "48_48") (pintype "passive"))
    )
    (net (code "248") (name "unconnected-(P2-Pad49)") (class "Default")
      (node (ref "P2") (pin "49") (pinfunction "49_49") (pintype "passive"))
    )
    (net (code "249") (name "unconnected-(P2-Pad50)") (class "Default")
      (node (ref "P2") (pin "50") (pinfunction "50_50") (pintype "passive"))
    )
    (net (code "250") (name "unconnected-(P2-Pad53)") (class "Default")
      (node (ref "P2") (pin "53") (pinfunction "53_53") (pintype "passive"))
    )
    (net (code "251") (name "unconnected-(P2-Pad54)") (class "Default")
      (node (ref "P2") (pin "54") (pinfunction "54_54") (pintype "passive"))
    )
    (net (code "252") (name "unconnected-(P2-Pad55)") (class "Default")
      (node (ref "P2") (pin "55") (pinfunction "55_55") (pintype "passive"))
    )
    (net (code "253") (name "unconnected-(P2-Pad56)") (class "Default")
      (node (ref "P2") (pin "56") (pinfunction "56_56") (pintype "passive"))
    )
    (net (code "254") (name "unconnected-(P2-Pad57)") (class "Default")
      (node (ref "P2") (pin "57") (pinfunction "57_57") (pintype "passive"))
    )
    (net (code "255") (name "unconnected-(P2-Pad58)") (class "Default")
      (node (ref "P2") (pin "58") (pinfunction "58_58") (pintype "passive"))
    )
    (net (code "256") (name "unconnected-(P2-Pad59)") (class "Default")
      (node (ref "P2") (pin "59") (pinfunction "59_59") (pintype "passive"))
    )
    (net (code "257") (name "unconnected-(P2-Pad60)") (class "Default")
      (node (ref "P2") (pin "60") (pinfunction "60_60") (pintype "passive"))
    )
    (net (code "258") (name "unconnected-(P2-PadHOLE)") (class "Default")
      (node (ref "P2") (pin "HOLE") (pinfunction "HOLE_HOLE") (pintype "passive"))
    )
    (net (code "259") (name "unconnected-(P3-Pad1)") (class "Default")
      (node (ref "P3") (pin "1") (pinfunction "1_1") (pintype "passive"))
    )
    (net (code "260") (name "unconnected-(P3-Pad2)") (class "Default")
      (node (ref "P3") (pin "2") (pinfunction "2_2") (pintype "passive"))
    )
    (net (code "261") (name "unconnected-(P3-Pad3)") (class "Default")
      (node (ref "P3") (pin "3") (pinfunction "3_3") (pintype "passive"))
    )
    (net (code "262") (name "unconnected-(P3-Pad4)") (class "Default")
      (node (ref "P3") (pin "4") (pinfunction "4_4") (pintype "passive"))
    )
    (net (code "263") (name "unconnected-(P3-Pad5)") (class "Default")
      (node (ref "P3") (pin "5") (pinfunction "5_5") (pintype "passive"))
    )
    (net (code "264") (name "unconnected-(P3-Pad6)") (class "Default")
      (node (ref "P3") (pin "6") (pinfunction "6_6") (pintype "passive"))
    )
    (net (code "265") (name "unconnected-(P3-Pad7)") (class "Default")
      (node (ref "P3") (pin "7") (pinfunction "7_7") (pintype "passive"))
    )
    (net (code "266") (name "unconnected-(P3-Pad8)") (class "Default")
      (node (ref "P3") (pin "8") (pinfunction "8_8") (pintype "passive"))
    )
    (net (code "267") (name "unconnected-(P3-Pad9)") (class "Default")
      (node (ref "P3") (pin "9") (pinfunction "9_9") (pintype "passive"))
    )
    (net (code "268") (name "unconnected-(P3-Pad10)") (class "Default")
      (node (ref "P3") (pin "10") (pinfunction "10_10") (pintype "passive"))
    )
    (net (code "269") (name "unconnected-(P3-Pad13)") (class "Default")
      (node (ref "P3") (pin "13") (pinfunction "13_13") (pintype "passive"))
    )
    (net (code "270") (name "unconnected-(P3-Pad14)") (class "Default")
      (node (ref "P3") (pin "14") (pinfunction "14_14") (pintype "passive"))
    )
    (net (code "271") (name "unconnected-(P3-Pad15)") (class "Default")
      (node (ref "P3") (pin "15") (pinfunction "15_15") (pintype "passive"))
    )
    (net (code "272") (name "unconnected-(P3-Pad16)") (class "Default")
      (node (ref "P3") (pin "16") (pinfunction "16_16") (pintype "passive"))
    )
    (net (code "273") (name "unconnected-(P3-Pad17)") (class "Default")
      (node (ref "P3") (pin "17") (pinfunction "17_17") (pintype "passive"))
    )
    (net (code "274") (name "unconnected-(P3-Pad18)") (class "Default")
      (node (ref "P3") (pin "18") (pinfunction "18_18") (pintype "passive"))
    )
    (net (code "275") (name "unconnected-(P3-Pad19)") (class "Default")
      (node (ref "P3") (pin "19") (pinfunction "19_19") (pintype "passive"))
    )
    (net (code "276") (name "unconnected-(P3-Pad20)") (class "Default")
      (node (ref "P3") (pin "20") (pinfunction "20_20") (pintype "passive"))
    )
    (net (code "277") (name "unconnected-(P3-Pad23)") (class "Default")
      (node (ref "P3") (pin "23") (pinfunction "23_23") (pintype "passive"))
    )
    (net (code "278") (name "unconnected-(P3-Pad24)") (class "Default")
      (node (ref "P3") (pin "24") (pinfunction "24_24") (pintype "passive"))
    )
    (net (code "279") (name "unconnected-(P3-Pad25)") (class "Default")
      (node (ref "P3") (pin "25") (pinfunction "25_25") (pintype "passive"))
    )
    (net (code "280") (name "unconnected-(P3-Pad26)") (class "Default")
      (node (ref "P3") (pin "26") (pinfunction "26_26") (pintype "passive"))
    )
    (net (code "281") (name "unconnected-(P3-Pad27)") (class "Default")
      (node (ref "P3") (pin "27") (pinfunction "27_27") (pintype "passive"))
    )
    (net (code "282") (name "unconnected-(P3-Pad28)") (class "Default")
      (node (ref "P3") (pin "28") (pinfunction "28_28") (pintype "passive"))
    )
    (net (code "283") (name "unconnected-(P3-Pad29)") (class "Default")
      (node (ref "P3") (pin "29") (pinfunction "29_29") (pintype "passive"))
    )
    (net (code "284") (name "unconnected-(P3-Pad30)") (class "Default")
      (node (ref "P3") (pin "30") (pinfunction "30_30") (pintype "passive"))
    )
    (net (code "285") (name "unconnected-(P3-Pad33)") (class "Default")
      (node (ref "P3") (pin "33") (pinfunction "33_33") (pintype "passive"))
    )
    (net (code "286") (name "unconnected-(P3-Pad34)") (class "Default")
      (node (ref "P3") (pin "34") (pinfunction "34_34") (pintype "passive"))
    )
    (net (code "287") (name "unconnected-(P3-Pad37)") (class "Default")
      (node (ref "P3") (pin "37") (pinfunction "37_37") (pintype "passive"))
    )
    (net (code "288") (name "unconnected-(P3-Pad38)") (class "Default")
      (node (ref "P3") (pin "38") (pinfunction "38_38") (pintype "passive"))
    )
    (net (code "289") (name "unconnected-(P3-Pad39)") (class "Default")
      (node (ref "P3") (pin "39") (pinfunction "39_39") (pintype "passive"))
    )
    (net (code "290") (name "unconnected-(P3-Pad40)") (class "Default")
      (node (ref "P3") (pin "40") (pinfunction "40_40") (pintype "passive"))
    )
    (net (code "291") (name "unconnected-(P3-Pad43)") (class "Default")
      (node (ref "P3") (pin "43") (pinfunction "43_43") (pintype "passive"))
    )
    (net (code "292") (name "unconnected-(P3-Pad44)") (class "Default")
      (node (ref "P3") (pin "44") (pinfunction "44_44") (pintype "passive"))
    )
    (net (code "293") (name "unconnected-(P3-Pad45)") (class "Default")
      (node (ref "P3") (pin "45") (pinfunction "45_45") (pintype "passive"))
    )
    (net (code "294") (name "unconnected-(P3-Pad46)") (class "Default")
      (node (ref "P3") (pin "46") (pinfunction "46_46") (pintype "passive"))
    )
    (net (code "295") (name "unconnected-(P3-Pad47)") (class "Default")
      (node (ref "P3") (pin "47") (pinfunction "47_47") (pintype "passive"))
    )
    (net (code "296") (name "unconnected-(P3-Pad48)") (class "Default")
      (node (ref "P3") (pin "48") (pinfunction "48_48") (pintype "passive"))
    )
    (net (code "297") (name "unconnected-(P3-Pad49)") (class "Default")
      (node (ref "P3") (pin "49") (pinfunction "49_49") (pintype "passive"))
    )
    (net (code "298") (name "unconnected-(P3-Pad50)") (class "Default")
      (node (ref "P3") (pin "50") (pinfunction "50_50") (pintype "passive"))
    )
    (net (code "299") (name "unconnected-(P3-Pad53)") (class "Default")
      (node (ref "P3") (pin "53") (pinfunction "53_53") (pintype "passive"))
    )
    (net (code "300") (name "unconnected-(P3-Pad54)") (class "Default")
      (node (ref "P3") (pin "54") (pinfunction "54_54") (pintype "passive"))
    )
    (net (code "301") (name "unconnected-(P3-Pad55)") (class "Default")
      (node (ref "P3") (pin "55") (pinfunction "55_55") (pintype "passive"))
    )
    (net (code "302") (name "unconnected-(P3-Pad56)") (class "Default")
      (node (ref "P3") (pin "56") (pinfunction "56_56") (pintype "passive"))
    )
    (net (code "303") (name "unconnected-(P3-Pad57)") (class "Default")
      (node (ref "P3") (pin "57") (pinfunction "57_57") (pintype "passive"))
    )
    (net (code "304") (name "unconnected-(P3-Pad58)") (class "Default")
      (node (ref "P3") (pin "58") (pinfunction "58_58") (pintype "passive"))
    )
    (net (code "305") (name "unconnected-(P3-Pad59)") (class "Default")
      (node (ref "P3") (pin "59") (pinfunction "59_59") (pintype "passive"))
    )
    (net (code "306") (name "unconnected-(P3-Pad60)") (class "Default")
      (node (ref "P3") (pin "60") (pinfunction "60_60") (pintype "passive"))
    )
    (net (code "307") (name "unconnected-(P3-PadHOLE)") (class "Default")
      (node (ref "P3") (pin "HOLE") (pinfunction "HOLE_HOLE") (pintype "passive"))
    )
    (net (code "308") (name "unconnected-(P4-Pad1)") (class "Default")
      (node (ref "P4") (pin "1") (pinfunction "1_1") (pintype "passive"))
    )
    (net (code "309") (name "unconnected-(P4-Pad2)") (class "Default")
      (node (ref "P4") (pin "2") (pinfunction "2_2") (pintype "passive"))
    )
    (net (code "310") (name "unconnected-(P4-Pad3)") (class "Default")
      (node (ref "P4") (pin "3") (pinfunction "3_3") (pintype "passive"))
    )
    (net (code "311") (name "unconnected-(P4-Pad4)") (class "Default")
      (node (ref "P4") (pin "4") (pinfunction "4_4") (pintype "passive"))
    )
    (net (code "312") (name "unconnected-(P4-Pad5)") (class "Default")
      (node (ref "P4") (pin "5") (pinfunction "5_5") (pintype "passive"))
    )
    (net (code "313") (name "unconnected-(P4-Pad6)") (class "Default")
      (node (ref "P4") (pin "6") (pinfunction "6_6") (pintype "passive"))
    )
    (net (code "314") (name "unconnected-(P4-Pad7)") (class "Default")
      (node (ref "P4") (pin "7") (pinfunction "7_7") (pintype "passive"))
    )
    (net (code "315") (name "unconnected-(P4-Pad8)") (class "Default")
      (node (ref "P4") (pin "8") (pinfunction "8_8") (pintype "passive"))
    )
    (net (code "316") (name "unconnected-(P4-Pad9)") (class "Default")
      (node (ref "P4") (pin "9") (pinfunction "9_9") (pintype "passive"))
    )
    (net (code "317") (name "unconnected-(P4-Pad10)") (class "Default")
      (node (ref "P4") (pin "10") (pinfunction "10_10") (pintype "passive"))
    )
    (net (code "318") (name "unconnected-(P4-Pad13)") (class "Default")
      (node (ref "P4") (pin "13") (pinfunction "13_13") (pintype "passive"))
    )
    (net (code "319") (name "unconnected-(P4-Pad14)") (class "Default")
      (node (ref "P4") (pin "14") (pinfunction "14_14") (pintype "passive"))
    )
    (net (code "320") (name "unconnected-(P4-Pad15)") (class "Default")
      (node (ref "P4") (pin "15") (pinfunction "15_15") (pintype "passive"))
    )
    (net (code "321") (name "unconnected-(P4-Pad16)") (class "Default")
      (node (ref "P4") (pin "16") (pinfunction "16_16") (pintype "passive"))
    )
    (net (code "322") (name "unconnected-(P4-Pad17)") (class "Default")
      (node (ref "P4") (pin "17") (pinfunction "17_17") (pintype "passive"))
    )
    (net (code "323") (name "unconnected-(P4-Pad18)") (class "Default")
      (node (ref "P4") (pin "18") (pinfunction "18_18") (pintype "passive"))
    )
    (net (code "324") (name "unconnected-(P4-Pad19)") (class "Default")
      (node (ref "P4") (pin "19") (pinfunction "19_19") (pintype "passive"))
    )
    (net (code "325") (name "unconnected-(P4-Pad20)") (class "Default")
      (node (ref "P4") (pin "20") (pinfunction "20_20") (pintype "passive"))
    )
    (net (code "326") (name "unconnected-(P4-Pad23)") (class "Default")
      (node (ref "P4") (pin "23") (pinfunction "23_23") (pintype "passive"))
    )
    (net (code "327") (name "unconnected-(P4-Pad24)") (class "Default")
      (node (ref "P4") (pin "24") (pinfunction "24_24") (pintype "passive"))
    )
    (net (code "328") (name "unconnected-(P4-Pad25)") (class "Default")
      (node (ref "P4") (pin "25") (pinfunction "25_25") (pintype "passive"))
    )
    (net (code "329") (name "unconnected-(P4-Pad26)") (class "Default")
      (node (ref "P4") (pin "26") (pinfunction "26_26") (pintype "passive"))
    )
    (net (code "330") (name "unconnected-(P4-Pad27)") (class "Default")
      (node (ref "P4") (pin "27") (pinfunction "27_27") (pintype "passive"))
    )
    (net (code "331") (name "unconnected-(P4-Pad28)") (class "Default")
      (node (ref "P4") (pin "28") (pinfunction "28_28") (pintype "passive"))
    )
    (net (code "332") (name "unconnected-(P4-Pad29)") (class "Default")
      (node (ref "P4") (pin "29") (pinfunction "29_29") (pintype "passive"))
    )
    (net (code "333") (name "unconnected-(P4-Pad30)") (class "Default")
      (node (ref "P4") (pin "30") (pinfunction "30_30") (pintype "passive"))
    )
    (net (code "334") (name "unconnected-(P4-Pad33)") (class "Default")
      (node (ref "P4") (pin "33") (pinfunction "33_33") (pintype "passive"))
    )
    (net (code "335") (name "unconnected-(P4-Pad34)") (class "Default")
      (node (ref "P4") (pin "34") (pinfunction "34_34") (pintype "passive"))
    )
    (net (code "336") (name "unconnected-(P4-Pad35)") (class "Default")
      (node (ref "P4") (pin "35") (pinfunction "35_35") (pintype "passive"))
    )
    (net (code "337") (name "unconnected-(P4-Pad36)") (class "Default")
      (node (ref "P4") (pin "36") (pinfunction "36_36") (pintype "passive"))
    )
    (net (code "338") (name "unconnected-(P4-Pad37)") (class "Default")
      (node (ref "P4") (pin "37") (pinfunction "37_37") (pintype "passive"))
    )
    (net (code "339") (name "unconnected-(P4-Pad38)") (class "Default")
      (node (ref "P4") (pin "38") (pinfunction "38_38") (pintype "passive"))
    )
    (net (code "340") (name "unconnected-(P4-Pad39)") (class "Default")
      (node (ref "P4") (pin "39") (pinfunction "39_39") (pintype "passive"))
    )
    (net (code "341") (name "unconnected-(P4-Pad40)") (class "Default")
      (node (ref "P4") (pin "40") (pinfunction "40_40") (pintype "passive"))
    )
    (net (code "342") (name "unconnected-(P4-Pad43)") (class "Default")
      (node (ref "P4") (pin "43") (pinfunction "43_43") (pintype "passive"))
    )
    (net (code "343") (name "unconnected-(P4-Pad44)") (class "Default")
      (node (ref "P4") (pin "44") (pinfunction "44_44") (pintype "passive"))
    )
    (net (code "344") (name "unconnected-(P4-Pad45)") (class "Default")
      (node (ref "P4") (pin "45") (pinfunction "45_45") (pintype "passive"))
    )
    (net (code "345") (name "unconnected-(P4-Pad46)") (class "Default")
      (node (ref "P4") (pin "46") (pinfunction "46_46") (pintype "passive"))
    )
    (net (code "346") (name "unconnected-(P4-Pad47)") (class "Default")
      (node (ref "P4") (pin "47") (pinfunction "47_47") (pintype "passive"))
    )
    (net (code "347") (name "unconnected-(P4-Pad48)") (class "Default")
      (node (ref "P4") (pin "48") (pinfunction "48_48") (pintype "passive"))
    )
    (net (code "348") (name "unconnected-(P4-Pad49)") (class "Default")
      (node (ref "P4") (pin "49") (pinfunction "49_49") (pintype "passive"))
    )
    (net (code "349") (name "unconnected-(P4-Pad50)") (class "Default")
      (node (ref "P4") (pin "50") (pinfunction "50_50") (pintype "passive"))
    )
    (net (code "350") (name "unconnected-(P4-Pad53)") (class "Default")
      (node (ref "P4") (pin "53") (pinfunction "53_53") (pintype "passive"))
    )
    (net (code "351") (name "unconnected-(P4-Pad54)") (class "Default")
      (node (ref "P4") (pin "54") (pinfunction "54_54") (pintype "passive"))
    )
    (net (code "352") (name "unconnected-(P4-Pad55)") (class "Default")
      (node (ref "P4") (pin "55") (pinfunction "55_55") (pintype "passive"))
    )
    (net (code "353") (name "unconnected-(P4-Pad56)") (class "Default")
      (node (ref "P4") (pin "56") (pinfunction "56_56") (pintype "passive"))
    )
    (net (code "354") (name "unconnected-(P4-Pad57)") (class "Default")
      (node (ref "P4") (pin "57") (pinfunction "57_57") (pintype "passive"))
    )
    (net (code "355") (name "unconnected-(P4-Pad58)") (class "Default")
      (node (ref "P4") (pin "58") (pinfunction "58_58") (pintype "passive"))
    )
    (net (code "356") (name "unconnected-(P4-Pad59)") (class "Default")
      (node (ref "P4") (pin "59") (pinfunction "59_59") (pintype "passive"))
    )
    (net (code "357") (name "unconnected-(P4-Pad60)") (class "Default")
      (node (ref "P4") (pin "60") (pinfunction "60_60") (pintype "passive"))
    )
    (net (code "358") (name "unconnected-(P4-PadHOLE)") (class "Default")
      (node (ref "P4") (pin "HOLE") (pinfunction "HOLE_HOLE") (pintype "passive"))
    )
    (net (code "359") (name "unconnected-(P17-Pad1)") (class "Default")
      (node (ref "P17") (pin "1") (pinfunction "1_1") (pintype "bidirectional+no_connect"))
    )
    (net (code "360") (name "unconnected-(P17-Pad12)") (class "Default")
      (node (ref "P17") (pin "12") (pinfunction "12_12") (pintype "bidirectional+no_connect"))
    )
    (net (code "361") (name "unconnected-(P17-Pad14)") (class "Default")
      (node (ref "P17") (pin "14") (pinfunction "14_14") (pintype "bidirectional+no_connect"))
    )
    (net (code "362") (name "unconnected-(P17-PadHOLE)") (class "Default")
      (node (ref "P17") (pin "HOLE") (pinfunction "HOLE_HOLE") (pintype "passive"))
    )
    (net (code "363") (name "unconnected-(P17-PadHOLE)_1") (class "Default")
      (node (ref "P17") (pin "HOLE") (pinfunction "HOLE_HOLE") (pintype "passive"))
    )
  )
)
